# Schaltplan_V1_0.net
KiCad netlist of a schematic drawn in EAGLE
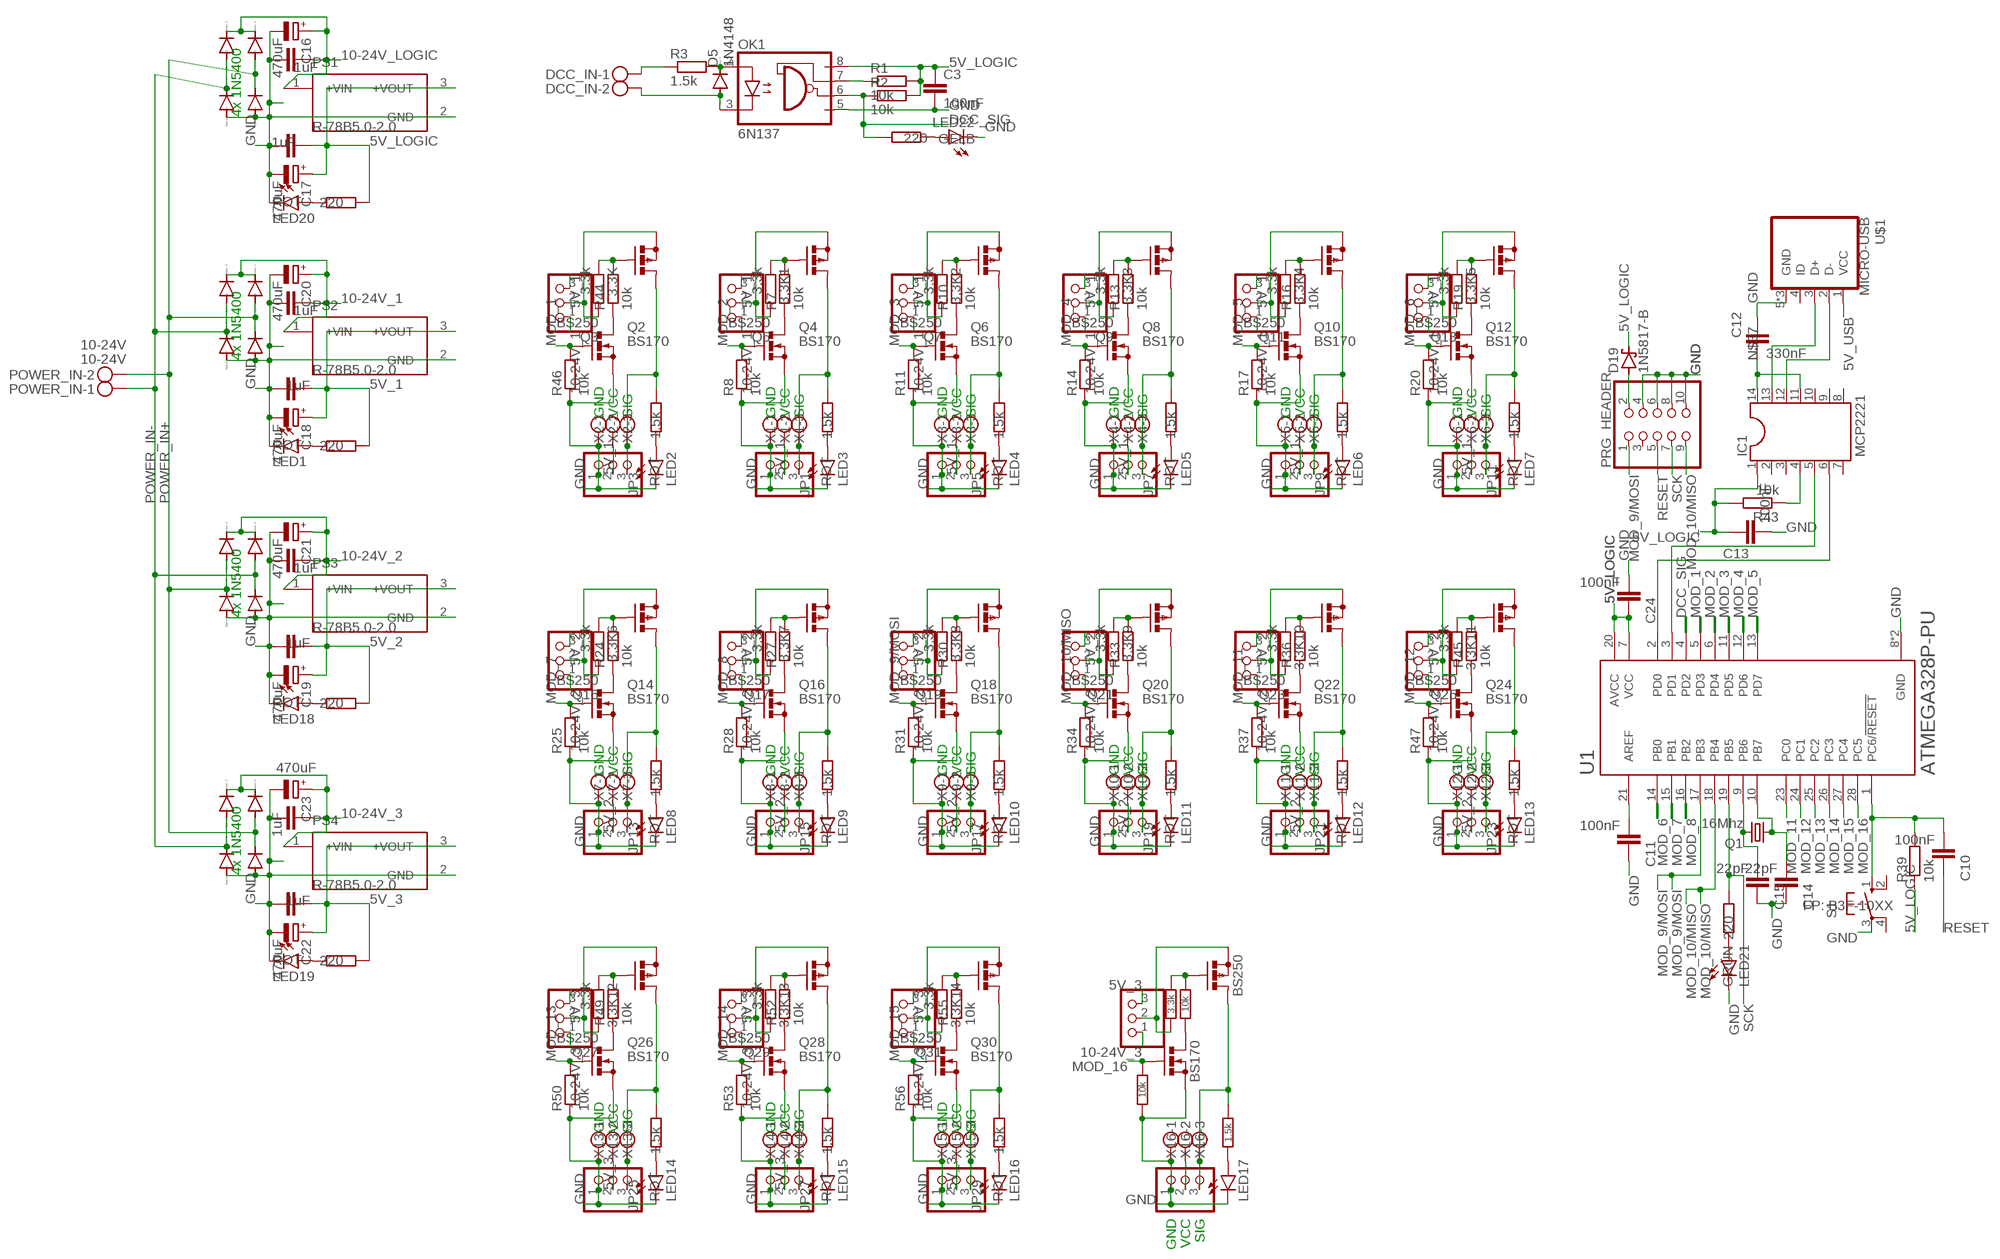
[diagram p0: schematic, sheet 1]

(export (version "E")
  (design (tool "Eeschema 10.0.6"))
  (components
    (comp (ref "3,3K")
      (value "3.3k")
      (footprint "eagle-import:0207_7")
      (libsource (lib "eagle-import") (part "R-EU_0207/7"))
    )
    (comp (ref "3,3K1")
      (value "3.3k")
      (footprint "eagle-import:0207_7")
      (libsource (lib "eagle-import") (part "R-EU_0207/7"))
    )
    (comp (ref "3,3K2")
      (value "3.3k")
      (footprint "eagle-import:0207_7")
      (libsource (lib "eagle-import") (part "R-EU_0207/7"))
    )
    (comp (ref "3,3K3")
      (value "3.3k")
      (footprint "eagle-import:0207_7")
      (libsource (lib "eagle-import") (part "R-EU_0207/7"))
    )
    (comp (ref "3,3K4")
      (value "3.3k")
      (footprint "eagle-import:0207_7")
      (libsource (lib "eagle-import") (part "R-EU_0207/7"))
    )
    (comp (ref "3,3K5")
      (value "3.3k")
      (footprint "eagle-import:0207_7")
      (libsource (lib "eagle-import") (part "R-EU_0207/7"))
    )
    (comp (ref "3,3K6")
      (value "3.3k")
      (footprint "eagle-import:0207_7")
      (libsource (lib "eagle-import") (part "R-EU_0207/7"))
    )
    (comp (ref "3,3K7")
      (value "3.3k")
      (footprint "eagle-import:0207_7")
      (libsource (lib "eagle-import") (part "R-EU_0207/7"))
    )
    (comp (ref "3,3K8")
      (value "3.3k")
      (footprint "eagle-import:0207_7")
      (libsource (lib "eagle-import") (part "R-EU_0207/7"))
    )
    (comp (ref "3,3K9")
      (value "3.3k")
      (footprint "eagle-import:0207_7")
      (libsource (lib "eagle-import") (part "R-EU_0207/7"))
    )
    (comp (ref "3,3K10")
      (value "3.3k")
      (footprint "eagle-import:0207_7")
      (libsource (lib "eagle-import") (part "R-EU_0207/7"))
    )
    (comp (ref "3,3K11")
      (value "3.3k")
      (footprint "eagle-import:0207_7")
      (libsource (lib "eagle-import") (part "R-EU_0207/7"))
    )
    (comp (ref "3,3K12")
      (value "3.3k")
      (footprint "eagle-import:0207_7")
      (libsource (lib "eagle-import") (part "R-EU_0207/7"))
    )
    (comp (ref "3,3K13")
      (value "3.3k")
      (footprint "eagle-import:0207_7")
      (libsource (lib "eagle-import") (part "R-EU_0207/7"))
    )
    (comp (ref "3,3K14")
      (value "3.3k")
      (footprint "eagle-import:0207_7")
      (libsource (lib "eagle-import") (part "R-EU_0207/7"))
    )
    (comp (ref "3,3K15")
      (value "3.3k")
      (footprint "eagle-import:0207_7")
      (libsource (lib "eagle-import") (part "R-EU_0207/7"))
    )
    (comp (ref "C1")
      (value "1uF")
      (footprint "eagle-import:C050-025X075")
      (libsource (lib "eagle-import") (part "C-EU050-025X075"))
    )
    (comp (ref "C2")
      (value "1uF")
      (footprint "eagle-import:C050-025X075")
      (libsource (lib "eagle-import") (part "C-EU050-025X075"))
    )
    (comp (ref "C3")
      (value "100nF")
      (footprint "eagle-import:C025-025X050")
      (libsource (lib "eagle-import") (part "C-EU025-025X050"))
    )
    (comp (ref "C4")
      (value "1uF")
      (footprint "eagle-import:C050-025X075")
      (libsource (lib "eagle-import") (part "C-EU050-025X075"))
    )
    (comp (ref "C5")
      (value "1uF")
      (footprint "eagle-import:C050-025X075")
      (libsource (lib "eagle-import") (part "C-EU050-025X075"))
    )
    (comp (ref "C6")
      (value "1uF")
      (footprint "eagle-import:C050-025X075")
      (libsource (lib "eagle-import") (part "C-EU050-025X075"))
    )
    (comp (ref "C7")
      (value "1uF")
      (footprint "eagle-import:C050-025X075")
      (libsource (lib "eagle-import") (part "C-EU050-025X075"))
    )
    (comp (ref "C8")
      (value "1uF")
      (footprint "eagle-import:C050-025X075")
      (libsource (lib "eagle-import") (part "C-EU050-025X075"))
    )
    (comp (ref "C9")
      (value "1uF")
      (footprint "eagle-import:C050-025X075")
      (libsource (lib "eagle-import") (part "C-EU050-025X075"))
    )
    (comp (ref "C10")
      (value "100nF")
      (footprint "eagle-import:C025-025X050")
      (libsource (lib "eagle-import") (part "C-EU025-025X050"))
    )
    (comp (ref "C11")
      (value "100nF")
      (footprint "eagle-import:C025-025X050")
      (libsource (lib "eagle-import") (part "C-EU025-025X050"))
    )
    (comp (ref "C12")
      (value "330nF")
      (footprint "eagle-import:C025-025X050")
      (libsource (lib "eagle-import") (part "C-EU025-025X050"))
    )
    (comp (ref "C13")
      (value "100nF")
      (footprint "eagle-import:C025-025X050")
      (libsource (lib "eagle-import") (part "C-EU025-025X050"))
    )
    (comp (ref "C14")
      (value "22pF")
      (footprint "eagle-import:C025-030X050")
      (libsource (lib "eagle-import") (part "C-EU025-030X050"))
    )
    (comp (ref "C15")
      (value "22pF")
      (footprint "eagle-import:C025-030X050")
      (libsource (lib "eagle-import") (part "C-EU025-030X050"))
    )
    (comp (ref "C16")
      (value "470uF")
      (footprint "eagle-import:E5-10,5")
      (libsource (lib "eagle-import") (part "CPOL-EUE5-10.5"))
    )
    (comp (ref "C17")
      (value "470uF")
      (footprint "eagle-import:E5-10,5")
      (libsource (lib "eagle-import") (part "CPOL-EUE5-10.5"))
    )
    (comp (ref "C18")
      (value "470uF")
      (footprint "eagle-import:E5-10,5")
      (libsource (lib "eagle-import") (part "CPOL-EUE5-10.5"))
    )
    (comp (ref "C19")
      (value "470uF")
      (footprint "eagle-import:E5-10,5")
      (libsource (lib "eagle-import") (part "CPOL-EUE5-10.5"))
    )
    (comp (ref "C20")
      (value "470uF")
      (footprint "eagle-import:E5-10,5")
      (libsource (lib "eagle-import") (part "CPOL-EUE5-10.5"))
    )
    (comp (ref "C21")
      (value "470uF")
      (footprint "eagle-import:E5-10,5")
      (libsource (lib "eagle-import") (part "CPOL-EUE5-10.5"))
    )
    (comp (ref "C22")
      (value "470uF")
      (footprint "eagle-import:E5-10,5")
      (libsource (lib "eagle-import") (part "CPOL-EUE5-10.5"))
    )
    (comp (ref "C23")
      (value "470uF")
      (footprint "eagle-import:E5-10,5")
      (libsource (lib "eagle-import") (part "CPOL-EUE5-10.5"))
    )
    (comp (ref "C24")
      (value "100nF")
      (footprint "eagle-import:C025-025X050")
      (libsource (lib "eagle-import") (part "C-EU025-025X050"))
    )
    (comp (ref "D1")
      (value "1N5400")
      (footprint "eagle-import:DO201-15")
      (libsource (lib "eagle-import") (part "1N5400"))
    )
    (comp (ref "D2")
      (value "1N5400")
      (footprint "eagle-import:DO201-15")
      (libsource (lib "eagle-import") (part "1N5400"))
    )
    (comp (ref "D3")
      (value "1N5400")
      (footprint "eagle-import:DO201-15")
      (libsource (lib "eagle-import") (part "1N5400"))
    )
    (comp (ref "D4")
      (value "1N5400")
      (footprint "eagle-import:DO201-15")
      (libsource (lib "eagle-import") (part "1N5400"))
    )
    (comp (ref "D5")
      (value "1N4148")
      (footprint "eagle-import:DO35-7")
      (libsource (lib "eagle-import") (part "1N4148DO35-7"))
    )
    (comp (ref "D6")
      (value "1N5400")
      (footprint "eagle-import:DO201-15")
      (libsource (lib "eagle-import") (part "1N5400"))
    )
    (comp (ref "D7")
      (value "1N5400")
      (footprint "eagle-import:DO201-15")
      (libsource (lib "eagle-import") (part "1N5400"))
    )
    (comp (ref "D8")
      (value "1N5400")
      (footprint "eagle-import:DO201-15")
      (libsource (lib "eagle-import") (part "1N5400"))
    )
    (comp (ref "D9")
      (value "1N5400")
      (footprint "eagle-import:DO201-15")
      (libsource (lib "eagle-import") (part "1N5400"))
    )
    (comp (ref "D10")
      (value "1N5400")
      (footprint "eagle-import:DO201-15")
      (libsource (lib "eagle-import") (part "1N5400"))
    )
    (comp (ref "D11")
      (value "1N5400")
      (footprint "eagle-import:DO201-15")
      (libsource (lib "eagle-import") (part "1N5400"))
    )
    (comp (ref "D12")
      (value "1N5400")
      (footprint "eagle-import:DO201-15")
      (libsource (lib "eagle-import") (part "1N5400"))
    )
    (comp (ref "D13")
      (value "1N5400")
      (footprint "eagle-import:DO201-15")
      (libsource (lib "eagle-import") (part "1N5400"))
    )
    (comp (ref "D14")
      (value "1N5400")
      (footprint "eagle-import:DO201-15")
      (libsource (lib "eagle-import") (part "1N5400"))
    )
    (comp (ref "D15")
      (value "1N5400")
      (footprint "eagle-import:DO201-15")
      (libsource (lib "eagle-import") (part "1N5400"))
    )
    (comp (ref "D16")
      (value "1N5400")
      (footprint "eagle-import:DO201-15")
      (libsource (lib "eagle-import") (part "1N5400"))
    )
    (comp (ref "D17")
      (value "1N5400")
      (footprint "eagle-import:DO201-15")
      (libsource (lib "eagle-import") (part "1N5400"))
    )
    (comp (ref "D19")
      (value "1N5817-B")
      (footprint "eagle-import:DO41-7.6")
      (libsource (lib "eagle-import") (part "1N5817-B"))
    )
    (comp (ref "DCC_IN")
      (value "MKDSN1,5/2-5,08")
      (footprint "eagle-import:MKDSN1,5_2-5,08")
      (libsource (lib "eagle-import") (part "MKDSN1,5/2-5,08"))
    )
    (comp (ref "IC1")
      (value "MCP2221")
      (footprint "eagle-import:DIL14")
      (libsource (lib "eagle-import") (part "DIL14"))
    )
    (comp (ref "JP1")
      (value "PINHD-1X3")
      (footprint "eagle-import:1X03")
      (libsource (lib "eagle-import") (part "PINHD-1X3"))
    )
    (comp (ref "JP2")
      (value "PINHD-1X3")
      (footprint "eagle-import:1X03")
      (libsource (lib "eagle-import") (part "PINHD-1X3"))
    )
    (comp (ref "JP3")
      (value "PINHD-1X3")
      (footprint "eagle-import:1X03")
      (libsource (lib "eagle-import") (part "PINHD-1X3"))
    )
    (comp (ref "JP4")
      (value "PINHD-1X3")
      (footprint "eagle-import:1X03")
      (libsource (lib "eagle-import") (part "PINHD-1X3"))
    )
    (comp (ref "JP5")
      (value "PINHD-1X3")
      (footprint "eagle-import:1X03")
      (libsource (lib "eagle-import") (part "PINHD-1X3"))
    )
    (comp (ref "JP6")
      (value "PINHD-1X3")
      (footprint "eagle-import:1X03")
      (libsource (lib "eagle-import") (part "PINHD-1X3"))
    )
    (comp (ref "JP7")
      (value "PINHD-1X3")
      (footprint "eagle-import:1X03")
      (libsource (lib "eagle-import") (part "PINHD-1X3"))
    )
    (comp (ref "JP8")
      (value "PINHD-1X3")
      (footprint "eagle-import:1X03")
      (libsource (lib "eagle-import") (part "PINHD-1X3"))
    )
    (comp (ref "JP9")
      (value "PINHD-1X3")
      (footprint "eagle-import:1X03")
      (libsource (lib "eagle-import") (part "PINHD-1X3"))
    )
    (comp (ref "JP10")
      (value "PINHD-1X3")
      (footprint "eagle-import:1X03")
      (libsource (lib "eagle-import") (part "PINHD-1X3"))
    )
    (comp (ref "JP11")
      (value "PINHD-1X3")
      (footprint "eagle-import:1X03")
      (libsource (lib "eagle-import") (part "PINHD-1X3"))
    )
    (comp (ref "JP12")
      (value "PINHD-1X3")
      (footprint "eagle-import:1X03")
      (libsource (lib "eagle-import") (part "PINHD-1X3"))
    )
    (comp (ref "JP13")
      (value "PINHD-1X3")
      (footprint "eagle-import:1X03")
      (libsource (lib "eagle-import") (part "PINHD-1X3"))
    )
    (comp (ref "JP14")
      (value "PINHD-1X3")
      (footprint "eagle-import:1X03")
      (libsource (lib "eagle-import") (part "PINHD-1X3"))
    )
    (comp (ref "JP15")
      (value "PINHD-1X3")
      (footprint "eagle-import:1X03")
      (libsource (lib "eagle-import") (part "PINHD-1X3"))
    )
    (comp (ref "JP16")
      (value "PINHD-1X3")
      (footprint "eagle-import:1X03")
      (libsource (lib "eagle-import") (part "PINHD-1X3"))
    )
    (comp (ref "JP17")
      (value "PINHD-1X3")
      (footprint "eagle-import:1X03")
      (libsource (lib "eagle-import") (part "PINHD-1X3"))
    )
    (comp (ref "JP18")
      (value "PINHD-1X3")
      (footprint "eagle-import:1X03")
      (libsource (lib "eagle-import") (part "PINHD-1X3"))
    )
    (comp (ref "JP19")
      (value "PINHD-1X3")
      (footprint "eagle-import:1X03")
      (libsource (lib "eagle-import") (part "PINHD-1X3"))
    )
    (comp (ref "JP20")
      (value "PINHD-1X3")
      (footprint "eagle-import:1X03")
      (libsource (lib "eagle-import") (part "PINHD-1X3"))
    )
    (comp (ref "JP21")
      (value "PINHD-1X3")
      (footprint "eagle-import:1X03")
      (libsource (lib "eagle-import") (part "PINHD-1X3"))
    )
    (comp (ref "JP22")
      (value "PINHD-1X3")
      (footprint "eagle-import:1X03")
      (libsource (lib "eagle-import") (part "PINHD-1X3"))
    )
    (comp (ref "JP23")
      (value "PINHD-1X3")
      (footprint "eagle-import:1X03")
      (libsource (lib "eagle-import") (part "PINHD-1X3"))
    )
    (comp (ref "JP24")
      (value "PINHD-1X3")
      (footprint "eagle-import:1X03")
      (libsource (lib "eagle-import") (part "PINHD-1X3"))
    )
    (comp (ref "JP25")
      (value "PINHD-1X3")
      (footprint "eagle-import:1X03")
      (libsource (lib "eagle-import") (part "PINHD-1X3"))
    )
    (comp (ref "JP26")
      (value "PINHD-1X3")
      (footprint "eagle-import:1X03")
      (libsource (lib "eagle-import") (part "PINHD-1X3"))
    )
    (comp (ref "JP27")
      (value "PINHD-1X3")
      (footprint "eagle-import:1X03")
      (libsource (lib "eagle-import") (part "PINHD-1X3"))
    )
    (comp (ref "JP28")
      (value "PINHD-1X3")
      (footprint "eagle-import:1X03")
      (libsource (lib "eagle-import") (part "PINHD-1X3"))
    )
    (comp (ref "JP29")
      (value "PINHD-1X3")
      (footprint "eagle-import:1X03")
      (libsource (lib "eagle-import") (part "PINHD-1X3"))
    )
    (comp (ref "JP30")
      (value "PINHD-1X3")
      (footprint "eagle-import:1X03")
      (libsource (lib "eagle-import") (part "PINHD-1X3"))
    )
    (comp (ref "JP31")
      (value "PINHD-1X3")
      (footprint "eagle-import:1X03")
      (libsource (lib "eagle-import") (part "PINHD-1X3"))
    )
    (comp (ref "JP32")
      (value "PINHD-1X3")
      (footprint "eagle-import:1X03")
      (libsource (lib "eagle-import") (part "PINHD-1X3"))
    )
    (comp (ref "LED1")
      (value "ROT")
      (footprint "eagle-import:LED3MM")
      (libsource (lib "eagle-import") (part "LED3MM"))
    )
    (comp (ref "LED2")
      (value "ROT")
      (footprint "eagle-import:LED3MM")
      (libsource (lib "eagle-import") (part "LED3MM"))
    )
    (comp (ref "LED3")
      (value "ROT")
      (footprint "eagle-import:LED3MM")
      (libsource (lib "eagle-import") (part "LED3MM"))
    )
    (comp (ref "LED4")
      (value "ROT")
      (footprint "eagle-import:LED3MM")
      (libsource (lib "eagle-import") (part "LED3MM"))
    )
    (comp (ref "LED5")
      (value "ROT")
      (footprint "eagle-import:LED3MM")
      (libsource (lib "eagle-import") (part "LED3MM"))
    )
    (comp (ref "LED6")
      (value "ROT")
      (footprint "eagle-import:LED3MM")
      (libsource (lib "eagle-import") (part "LED3MM"))
    )
    (comp (ref "LED7")
      (value "ROT")
      (footprint "eagle-import:LED3MM")
      (libsource (lib "eagle-import") (part "LED3MM"))
    )
    (comp (ref "LED8")
      (value "ROT")
      (footprint "eagle-import:LED3MM")
      (libsource (lib "eagle-import") (part "LED3MM"))
    )
    (comp (ref "LED9")
      (value "ROT")
      (footprint "eagle-import:LED3MM")
      (libsource (lib "eagle-import") (part "LED3MM"))
    )
    (comp (ref "LED10")
      (value "ROT")
      (footprint "eagle-import:LED3MM")
      (libsource (lib "eagle-import") (part "LED3MM"))
    )
    (comp (ref "LED11")
      (value "ROT")
      (footprint "eagle-import:LED3MM")
      (libsource (lib "eagle-import") (part "LED3MM"))
    )
    (comp (ref "LED12")
      (value "ROT")
      (footprint "eagle-import:LED3MM")
      (libsource (lib "eagle-import") (part "LED3MM"))
    )
    (comp (ref "LED13")
      (value "ROT")
      (footprint "eagle-import:LED3MM")
      (libsource (lib "eagle-import") (part "LED3MM"))
    )
    (comp (ref "LED14")
      (value "ROT")
      (footprint "eagle-import:LED3MM")
      (libsource (lib "eagle-import") (part "LED3MM"))
    )
    (comp (ref "LED15")
      (value "ROT")
      (footprint "eagle-import:LED3MM")
      (libsource (lib "eagle-import") (part "LED3MM"))
    )
    (comp (ref "LED16")
      (value "ROT")
      (footprint "eagle-import:LED3MM")
      (libsource (lib "eagle-import") (part "LED3MM"))
    )
    (comp (ref "LED17")
      (value "ROT")
      (footprint "eagle-import:LED3MM")
      (libsource (lib "eagle-import") (part "LED3MM"))
    )
    (comp (ref "LED18")
      (value "ROT")
      (footprint "eagle-import:LED3MM")
      (libsource (lib "eagle-import") (part "LED3MM"))
    )
    (comp (ref "LED19")
      (value "ROT")
      (footprint "eagle-import:LED3MM")
      (libsource (lib "eagle-import") (part "LED3MM"))
    )
    (comp (ref "LED20")
      (value "ROT")
      (footprint "eagle-import:LED3MM")
      (libsource (lib "eagle-import") (part "LED3MM"))
    )
    (comp (ref "LED21")
      (value "GRÜN")
      (footprint "eagle-import:LED3MM")
      (libsource (lib "eagle-import") (part "LED3MM"))
    )
    (comp (ref "LED22")
      (value "GELB")
      (footprint "eagle-import:LED3MM")
      (libsource (lib "eagle-import") (part "LED3MM"))
    )
    (comp (ref "OK1")
      (value "6N137")
      (footprint "eagle-import:DIL08")
      (libsource (lib "eagle-import") (part "6N137"))
    )
    (comp (ref "POWER_IN")
      (value "10-24V")
      (footprint "eagle-import:MKDSN1,5_2-5,08")
      (libsource (lib "eagle-import") (part "MKDSN1,5/2-5,08"))
    )
    (comp (ref "PRG_HEADER")
      (value "PINHD-2X5")
      (footprint "eagle-import:2X05")
      (libsource (lib "eagle-import") (part "PINHD-2X5"))
    )
    (comp (ref "PS1")
      (value "R-78B5.0-2.0")
      (footprint "eagle-import:CONV_R-78B5.0-2.0")
      (fields (field (name "MF") "Recom Power"))
      (libsource (lib "eagle-import") (part "R-78B5.0-2.0"))
    )
    (comp (ref "PS2")
      (value "R-78B5.0-2.0")
      (footprint "eagle-import:CONV_R-78B5.0-2.0")
      (fields (field (name "MF") "Recom Power"))
      (libsource (lib "eagle-import") (part "R-78B5.0-2.0"))
    )
    (comp (ref "PS3")
      (value "R-78B5.0-2.0")
      (footprint "eagle-import:CONV_R-78B5.0-2.0")
      (fields (field (name "MF") "Recom Power"))
      (libsource (lib "eagle-import") (part "R-78B5.0-2.0"))
    )
    (comp (ref "PS4")
      (value "R-78B5.0-2.0")
      (footprint "eagle-import:CONV_R-78B5.0-2.0")
      (fields (field (name "MF") "Recom Power"))
      (libsource (lib "eagle-import") (part "R-78B5.0-2.0"))
    )
    (comp (ref "Q1")
      (value "16Mhz")
      (footprint "eagle-import:HC49U-V")
      (libsource (lib "eagle-import") (part "CRYSTALHC49U-V"))
    )
    (comp (ref "Q2")
      (value "BS170")
      (footprint "eagle-import:SOT54E")
      (libsource (lib "eagle-import") (part "BS170"))
    )
    (comp (ref "Q3")
      (value "BS250")
      (footprint "eagle-import:SOT54E")
      (libsource (lib "eagle-import") (part "BS250"))
    )
    (comp (ref "Q4")
      (value "BS170")
      (footprint "eagle-import:SOT54E")
      (libsource (lib "eagle-import") (part "BS170"))
    )
    (comp (ref "Q5")
      (value "BS250")
      (footprint "eagle-import:SOT54E")
      (libsource (lib "eagle-import") (part "BS250"))
    )
    (comp (ref "Q6")
      (value "BS170")
      (footprint "eagle-import:SOT54E")
      (libsource (lib "eagle-import") (part "BS170"))
    )
    (comp (ref "Q7")
      (value "BS250")
      (footprint "eagle-import:SOT54E")
      (libsource (lib "eagle-import") (part "BS250"))
    )
    (comp (ref "Q8")
      (value "BS170")
      (footprint "eagle-import:SOT54E")
      (libsource (lib "eagle-import") (part "BS170"))
    )
    (comp (ref "Q9")
      (value "BS250")
      (footprint "eagle-import:SOT54E")
      (libsource (lib "eagle-import") (part "BS250"))
    )
    (comp (ref "Q10")
      (value "BS170")
      (footprint "eagle-import:SOT54E")
      (libsource (lib "eagle-import") (part "BS170"))
    )
    (comp (ref "Q11")
      (value "BS250")
      (footprint "eagle-import:SOT54E")
      (libsource (lib "eagle-import") (part "BS250"))
    )
    (comp (ref "Q12")
      (value "BS170")
      (footprint "eagle-import:SOT54E")
      (libsource (lib "eagle-import") (part "BS170"))
    )
    (comp (ref "Q13")
      (value "BS250")
      (footprint "eagle-import:SOT54E")
      (libsource (lib "eagle-import") (part "BS250"))
    )
    (comp (ref "Q14")
      (value "BS170")
      (footprint "eagle-import:SOT54E")
      (libsource (lib "eagle-import") (part "BS170"))
    )
    (comp (ref "Q15")
      (value "BS250")
      (footprint "eagle-import:SOT54E")
      (libsource (lib "eagle-import") (part "BS250"))
    )
    (comp (ref "Q16")
      (value "BS170")
      (footprint "eagle-import:SOT54E")
      (libsource (lib "eagle-import") (part "BS170"))
    )
    (comp (ref "Q17")
      (value "BS250")
      (footprint "eagle-import:SOT54E")
      (libsource (lib "eagle-import") (part "BS250"))
    )
    (comp (ref "Q18")
      (value "BS170")
      (footprint "eagle-import:SOT54E")
      (libsource (lib "eagle-import") (part "BS170"))
    )
    (comp (ref "Q19")
      (value "BS250")
      (footprint "eagle-import:SOT54E")
      (libsource (lib "eagle-import") (part "BS250"))
    )
    (comp (ref "Q20")
      (value "BS170")
      (footprint "eagle-import:SOT54E")
      (libsource (lib "eagle-import") (part "BS170"))
    )
    (comp (ref "Q21")
      (value "BS250")
      (footprint "eagle-import:SOT54E")
      (libsource (lib "eagle-import") (part "BS250"))
    )
    (comp (ref "Q22")
      (value "BS170")
      (footprint "eagle-import:SOT54E")
      (libsource (lib "eagle-import") (part "BS170"))
    )
    (comp (ref "Q23")
      (value "BS250")
      (footprint "eagle-import:SOT54E")
      (libsource (lib "eagle-import") (part "BS250"))
    )
    (comp (ref "Q24")
      (value "BS170")
      (footprint "eagle-import:SOT54E")
      (libsource (lib "eagle-import") (part "BS170"))
    )
    (comp (ref "Q25")
      (value "BS250")
      (footprint "eagle-import:SOT54E")
      (libsource (lib "eagle-import") (part "BS250"))
    )
    (comp (ref "Q26")
      (value "BS170")
      (footprint "eagle-import:SOT54E")
      (libsource (lib "eagle-import") (part "BS170"))
    )
    (comp (ref "Q27")
      (value "BS250")
      (footprint "eagle-import:SOT54E")
      (libsource (lib "eagle-import") (part "BS250"))
    )
    (comp (ref "Q28")
      (value "BS170")
      (footprint "eagle-import:SOT54E")
      (libsource (lib "eagle-import") (part "BS170"))
    )
    (comp (ref "Q29")
      (value "BS250")
      (footprint "eagle-import:SOT54E")
      (libsource (lib "eagle-import") (part "BS250"))
    )
    (comp (ref "Q30")
      (value "BS170")
      (footprint "eagle-import:SOT54E")
      (libsource (lib "eagle-import") (part "BS170"))
    )
    (comp (ref "Q31")
      (value "BS250")
      (footprint "eagle-import:SOT54E")
      (libsource (lib "eagle-import") (part "BS250"))
    )
    (comp (ref "Q32")
      (value "BS170")
      (footprint "eagle-import:SOT54E")
      (libsource (lib "eagle-import") (part "BS170"))
    )
    (comp (ref "Q33")
      (value "BS250")
      (footprint "eagle-import:SOT54E")
      (libsource (lib "eagle-import") (part "BS250"))
    )
    (comp (ref "R1")
      (value "10k")
      (footprint "eagle-import:0207_7")
      (libsource (lib "eagle-import") (part "R-EU_0207/7"))
    )
    (comp (ref "R2")
      (value "10k")
      (footprint "eagle-import:0207_7")
      (libsource (lib "eagle-import") (part "R-EU_0207/7"))
    )
    (comp (ref "R3")
      (value "1.5k")
      (footprint "eagle-import:0207_7")
      (libsource (lib "eagle-import") (part "R-EU_0207/7"))
    )
    (comp (ref "R4")
      (value "220")
      (footprint "eagle-import:0207_7")
      (libsource (lib "eagle-import") (part "R-EU_0207/7"))
    )
    (comp (ref "R5")
      (value "1.5k")
      (footprint "eagle-import:0207_7")
      (libsource (lib "eagle-import") (part "R-EU_0207/7"))
    )
    (comp (ref "R6")
      (value "1.5k")
      (footprint "eagle-import:0207_7")
      (libsource (lib "eagle-import") (part "R-EU_0207/7"))
    )
    (comp (ref "R7")
      (value "10k")
      (footprint "eagle-import:0207_7")
      (libsource (lib "eagle-import") (part "R-EU_0207/7"))
    )
    (comp (ref "R8")
      (value "10k")
      (footprint "eagle-import:0207_7")
      (libsource (lib "eagle-import") (part "R-EU_0207/7"))
    )
    (comp (ref "R9")
      (value "1.5k")
      (footprint "eagle-import:0207_7")
      (libsource (lib "eagle-import") (part "R-EU_0207/7"))
    )
    (comp (ref "R10")
      (value "10k")
      (footprint "eagle-import:0207_7")
      (libsource (lib "eagle-import") (part "R-EU_0207/7"))
    )
    (comp (ref "R11")
      (value "10k")
      (footprint "eagle-import:0207_7")
      (libsource (lib "eagle-import") (part "R-EU_0207/7"))
    )
    (comp (ref "R12")
      (value "1.5k")
      (footprint "eagle-import:0207_7")
      (libsource (lib "eagle-import") (part "R-EU_0207/7"))
    )
    (comp (ref "R13")
      (value "10k")
      (footprint "eagle-import:0207_7")
      (libsource (lib "eagle-import") (part "R-EU_0207/7"))
    )
    (comp (ref "R14")
      (value "10k")
      (footprint "eagle-import:0207_7")
      (libsource (lib "eagle-import") (part "R-EU_0207/7"))
    )
    (comp (ref "R15")
      (value "1.5k")
      (footprint "eagle-import:0207_7")
      (libsource (lib "eagle-import") (part "R-EU_0207/7"))
    )
    (comp (ref "R16")
      (value "10k")
      (footprint "eagle-import:0207_7")
      (libsource (lib "eagle-import") (part "R-EU_0207/7"))
    )
    (comp (ref "R17")
      (value "10k")
      (footprint "eagle-import:0207_7")
      (libsource (lib "eagle-import") (part "R-EU_0207/7"))
    )
    (comp (ref "R18")
      (value "1.5k")
      (footprint "eagle-import:0207_7")
      (libsource (lib "eagle-import") (part "R-EU_0207/7"))
    )
    (comp (ref "R19")
      (value "10k")
      (footprint "eagle-import:0207_7")
      (libsource (lib "eagle-import") (part "R-EU_0207/7"))
    )
    (comp (ref "R20")
      (value "10k")
      (footprint "eagle-import:0207_7")
      (libsource (lib "eagle-import") (part "R-EU_0207/7"))
    )
    (comp (ref "R21")
      (value "220")
      (footprint "eagle-import:0207_7")
      (libsource (lib "eagle-import") (part "R-EU_0207/7"))
    )
    (comp (ref "R22")
      (value "220")
      (footprint "eagle-import:0207_7")
      (libsource (lib "eagle-import") (part "R-EU_0207/7"))
    )
    (comp (ref "R23")
      (value "1.5k")
      (footprint "eagle-import:0207_7")
      (libsource (lib "eagle-import") (part "R-EU_0207/7"))
    )
    (comp (ref "R24")
      (value "10k")
      (footprint "eagle-import:0207_7")
      (libsource (lib "eagle-import") (part "R-EU_0207/7"))
    )
    (comp (ref "R25")
      (value "10k")
      (footprint "eagle-import:0207_7")
      (libsource (lib "eagle-import") (part "R-EU_0207/7"))
    )
    (comp (ref "R26")
      (value "1.5k")
      (footprint "eagle-import:0207_7")
      (libsource (lib "eagle-import") (part "R-EU_0207/7"))
    )
    (comp (ref "R27")
      (value "10k")
      (footprint "eagle-import:0207_7")
      (libsource (lib "eagle-import") (part "R-EU_0207/7"))
    )
    (comp (ref "R28")
      (value "10k")
      (footprint "eagle-import:0207_7")
      (libsource (lib "eagle-import") (part "R-EU_0207/7"))
    )
    (comp (ref "R29")
      (value "1.5k")
      (footprint "eagle-import:0207_7")
      (libsource (lib "eagle-import") (part "R-EU_0207/7"))
    )
    (comp (ref "R30")
      (value "10k")
      (footprint "eagle-import:0207_7")
      (libsource (lib "eagle-import") (part "R-EU_0207/7"))
    )
    (comp (ref "R31")
      (value "10k")
      (footprint "eagle-import:0207_7")
      (libsource (lib "eagle-import") (part "R-EU_0207/7"))
    )
    (comp (ref "R32")
      (value "1.5k")
      (footprint "eagle-import:0207_7")
      (libsource (lib "eagle-import") (part "R-EU_0207/7"))
    )
    (comp (ref "R33")
      (value "10k")
      (footprint "eagle-import:0207_7")
      (libsource (lib "eagle-import") (part "R-EU_0207/7"))
    )
    (comp (ref "R34")
      (value "10k")
      (footprint "eagle-import:0207_7")
      (libsource (lib "eagle-import") (part "R-EU_0207/7"))
    )
    (comp (ref "R35")
      (value "1.5k")
      (footprint "eagle-import:0207_7")
      (libsource (lib "eagle-import") (part "R-EU_0207/7"))
    )
    (comp (ref "R36")
      (value "10k")
      (footprint "eagle-import:0207_7")
      (libsource (lib "eagle-import") (part "R-EU_0207/7"))
    )
    (comp (ref "R37")
      (value "10k")
      (footprint "eagle-import:0207_7")
      (libsource (lib "eagle-import") (part "R-EU_0207/7"))
    )
    (comp (ref "R38")
      (value "1.5k")
      (footprint "eagle-import:0207_7")
      (libsource (lib "eagle-import") (part "R-EU_0207/7"))
    )
    (comp (ref "R39")
      (value "10k")
      (footprint "eagle-import:0207_7")
      (libsource (lib "eagle-import") (part "R-EU_0207/7"))
    )
    (comp (ref "R40")
      (value "220")
      (footprint "eagle-import:0207_7")
      (libsource (lib "eagle-import") (part "R-EU_0207/7"))
    )
    (comp (ref "R41")
      (value "220")
      (footprint "eagle-import:0207_7")
      (libsource (lib "eagle-import") (part "R-EU_0207/7"))
    )
    (comp (ref "R42")
      (value "220")
      (footprint "eagle-import:0207_7")
      (libsource (lib "eagle-import") (part "R-EU_0207/7"))
    )
    (comp (ref "R43")
      (value "10k")
      (footprint "eagle-import:0207_7")
      (libsource (lib "eagle-import") (part "R-EU_0207/7"))
    )
    (comp (ref "R44")
      (value "10k")
      (footprint "eagle-import:0207_7")
      (libsource (lib "eagle-import") (part "R-EU_0207/7"))
    )
    (comp (ref "R45")
      (value "10k")
      (footprint "eagle-import:0207_7")
      (libsource (lib "eagle-import") (part "R-EU_0207/7"))
    )
    (comp (ref "R46")
      (value "10k")
      (footprint "eagle-import:0207_7")
      (libsource (lib "eagle-import") (part "R-EU_0207/7"))
    )
    (comp (ref "R47")
      (value "10k")
      (footprint "eagle-import:0207_7")
      (libsource (lib "eagle-import") (part "R-EU_0207/7"))
    )
    (comp (ref "R48")
      (value "1.5k")
      (footprint "eagle-import:0207_7")
      (libsource (lib "eagle-import") (part "R-EU_0207/7"))
    )
    (comp (ref "R49")
      (value "10k")
      (footprint "eagle-import:0207_7")
      (libsource (lib "eagle-import") (part "R-EU_0207/7"))
    )
    (comp (ref "R50")
      (value "10k")
      (footprint "eagle-import:0207_7")
      (libsource (lib "eagle-import") (part "R-EU_0207/7"))
    )
    (comp (ref "R51")
      (value "1.5k")
      (footprint "eagle-import:0207_7")
      (libsource (lib "eagle-import") (part "R-EU_0207/7"))
    )
    (comp (ref "R52")
      (value "10k")
      (footprint "eagle-import:0207_7")
      (libsource (lib "eagle-import") (part "R-EU_0207/7"))
    )
    (comp (ref "R53")
      (value "10k")
      (footprint "eagle-import:0207_7")
      (libsource (lib "eagle-import") (part "R-EU_0207/7"))
    )
    (comp (ref "R54")
      (value "1.5k")
      (footprint "eagle-import:0207_7")
      (libsource (lib "eagle-import") (part "R-EU_0207/7"))
    )
    (comp (ref "R55")
      (value "10k")
      (footprint "eagle-import:0207_7")
      (libsource (lib "eagle-import") (part "R-EU_0207/7"))
    )
    (comp (ref "R56")
      (value "10k")
      (footprint "eagle-import:0207_7")
      (libsource (lib "eagle-import") (part "R-EU_0207/7"))
    )
    (comp (ref "R57")
      (value "1.5k")
      (footprint "eagle-import:0207_7")
      (libsource (lib "eagle-import") (part "R-EU_0207/7"))
    )
    (comp (ref "R58")
      (value "10k")
      (footprint "eagle-import:0207_7")
      (libsource (lib "eagle-import") (part "R-EU_0207/7"))
    )
    (comp (ref "R59")
      (value "10k")
      (footprint "eagle-import:0207_7")
      (libsource (lib "eagle-import") (part "R-EU_0207/7"))
    )
    (comp (ref "S1")
      (value "FP: B3F-10XX")
      (footprint "eagle-import:B3F-10XX")
      (fields (field (name "MPN") "B3F-1000"))
      (libsource (lib "eagle-import") (part "10-XX"))
    )
    (comp (ref "U$1")
      (value "MICRO-USB")
      (footprint "eagle-import:MICRO-USB")
      (libsource (lib "eagle-import") (part "MICRO-USB"))
    )
    (comp (ref "U1")
      (value "ATMEGA328P-PU")
      (footprint "eagle-import:DIP794W46P254L2967H457Q28B")
      (fields (field (name "MF") "Microchip"))
      (libsource (lib "eagle-import") (part "ATMEGA328P-PU"))
    )
    (comp (ref "X1")
      (value "MKDSN1,5/3-5,08")
      (footprint "eagle-import:MKDSN1,5_3-5,08")
      (libsource (lib "eagle-import") (part "MKDSN1,5/3-5,08"))
    )
    (comp (ref "X2")
      (value "MKDSN1,5/3-5,08")
      (footprint "eagle-import:MKDSN1,5_3-5,08")
      (libsource (lib "eagle-import") (part "MKDSN1,5/3-5,08"))
    )
    (comp (ref "X3")
      (value "MKDSN1,5/3-5,08")
      (footprint "eagle-import:MKDSN1,5_3-5,08")
      (libsource (lib "eagle-import") (part "MKDSN1,5/3-5,08"))
    )
    (comp (ref "X4")
      (value "MKDSN1,5/3-5,08")
      (footprint "eagle-import:MKDSN1,5_3-5,08")
      (libsource (lib "eagle-import") (part "MKDSN1,5/3-5,08"))
    )
    (comp (ref "X5")
      (value "MKDSN1,5/3-5,08")
      (footprint "eagle-import:MKDSN1,5_3-5,08")
      (libsource (lib "eagle-import") (part "MKDSN1,5/3-5,08"))
    )
    (comp (ref "X6")
      (value "MKDSN1,5/3-5,08")
      (footprint "eagle-import:MKDSN1,5_3-5,08")
      (libsource (lib "eagle-import") (part "MKDSN1,5/3-5,08"))
    )
    (comp (ref "X7")
      (value "MKDSN1,5/3-5,08")
      (footprint "eagle-import:MKDSN1,5_3-5,08")
      (libsource (lib "eagle-import") (part "MKDSN1,5/3-5,08"))
    )
    (comp (ref "X8")
      (value "MKDSN1,5/3-5,08")
      (footprint "eagle-import:MKDSN1,5_3-5,08")
      (libsource (lib "eagle-import") (part "MKDSN1,5/3-5,08"))
    )
    (comp (ref "X9")
      (value "MKDSN1,5/3-5,08")
      (footprint "eagle-import:MKDSN1,5_3-5,08")
      (libsource (lib "eagle-import") (part "MKDSN1,5/3-5,08"))
    )
    (comp (ref "X10")
      (value "MKDSN1,5/3-5,08")
      (footprint "eagle-import:MKDSN1,5_3-5,08")
      (libsource (lib "eagle-import") (part "MKDSN1,5/3-5,08"))
    )
    (comp (ref "X11")
      (value "MKDSN1,5/3-5,08")
      (footprint "eagle-import:MKDSN1,5_3-5,08")
      (libsource (lib "eagle-import") (part "MKDSN1,5/3-5,08"))
    )
    (comp (ref "X12")
      (value "MKDSN1,5/3-5,08")
      (footprint "eagle-import:MKDSN1,5_3-5,08")
      (libsource (lib "eagle-import") (part "MKDSN1,5/3-5,08"))
    )
    (comp (ref "X13")
      (value "MKDSN1,5/3-5,08")
      (footprint "eagle-import:MKDSN1,5_3-5,08")
      (libsource (lib "eagle-import") (part "MKDSN1,5/3-5,08"))
    )
    (comp (ref "X14")
      (value "MKDSN1,5/3-5,08")
      (footprint "eagle-import:MKDSN1,5_3-5,08")
      (libsource (lib "eagle-import") (part "MKDSN1,5/3-5,08"))
    )
    (comp (ref "X15")
      (value "MKDSN1,5/3-5,08")
      (footprint "eagle-import:MKDSN1,5_3-5,08")
      (libsource (lib "eagle-import") (part "MKDSN1,5/3-5,08"))
    )
    (comp (ref "X16")
      (value "MKDSN1,5/3-5,08")
      (footprint "eagle-import:MKDSN1,5_3-5,08")
      (libsource (lib "eagle-import") (part "MKDSN1,5/3-5,08"))
    )
  )
  (nets
    (net (code "1") (name "/5V_1") (class "Default")
      (node (ref "C1") (pin "2") (pinfunction "2_2") (pintype "passive"))
      (node (ref "C18") (pin "+") (pinfunction "+_+") (pintype "passive"))
      (node (ref "JP1") (pin "2") (pinfunction "2_2") (pintype "passive"))
      (node (ref "JP10") (pin "3") (pinfunction "3_3") (pintype "passive"))
      (node (ref "JP11") (pin "2") (pinfunction "2_2") (pintype "passive"))
      (node (ref "JP12") (pin "3") (pinfunction "3_3") (pintype "passive"))
      (node (ref "JP2") (pin "3") (pinfunction "3_3") (pintype "passive"))
      (node (ref "JP3") (pin "2") (pinfunction "2_2") (pintype "passive"))
      (node (ref "JP4") (pin "3") (pinfunction "3_3") (pintype "passive"))
      (node (ref "JP5") (pin "2") (pinfunction "2_2") (pintype "passive"))
      (node (ref "JP6") (pin "3") (pinfunction "3_3") (pintype "passive"))
      (node (ref "JP7") (pin "2") (pinfunction "2_2") (pintype "passive"))
      (node (ref "JP8") (pin "3") (pinfunction "3_3") (pintype "passive"))
      (node (ref "JP9") (pin "2") (pinfunction "2_2") (pintype "passive"))
      (node (ref "PS2") (pin "3") (pinfunction "+VOUT_3") (pintype "output"))
      (node (ref "R4") (pin "2") (pinfunction "2_2") (pintype "passive"))
      (node (ref "X1") (pin "2") (pinfunction "KL_2") (pintype "passive"))
      (node (ref "X2") (pin "2") (pinfunction "KL_2") (pintype "passive"))
      (node (ref "X3") (pin "2") (pinfunction "KL_2") (pintype "passive"))
      (node (ref "X4") (pin "2") (pinfunction "KL_2") (pintype "passive"))
      (node (ref "X5") (pin "2") (pinfunction "KL_2") (pintype "passive"))
      (node (ref "X6") (pin "2") (pinfunction "KL_2") (pintype "passive"))
    )
    (net (code "2") (name "/5V_2") (class "Default")
      (node (ref "C19") (pin "+") (pinfunction "+_+") (pintype "passive"))
      (node (ref "C4") (pin "2") (pinfunction "2_2") (pintype "passive"))
      (node (ref "JP13") (pin "2") (pinfunction "2_2") (pintype "passive"))
      (node (ref "JP14") (pin "3") (pinfunction "3_3") (pintype "passive"))
      (node (ref "JP15") (pin "2") (pinfunction "2_2") (pintype "passive"))
      (node (ref "JP16") (pin "3") (pinfunction "3_3") (pintype "passive"))
      (node (ref "JP17") (pin "2") (pinfunction "2_2") (pintype "passive"))
      (node (ref "JP18") (pin "3") (pinfunction "3_3") (pintype "passive"))
      (node (ref "JP19") (pin "2") (pinfunction "2_2") (pintype "passive"))
      (node (ref "JP20") (pin "3") (pinfunction "3_3") (pintype "passive"))
      (node (ref "JP21") (pin "2") (pinfunction "2_2") (pintype "passive"))
      (node (ref "JP22") (pin "3") (pinfunction "3_3") (pintype "passive"))
      (node (ref "JP23") (pin "2") (pinfunction "2_2") (pintype "passive"))
      (node (ref "JP24") (pin "3") (pinfunction "3_3") (pintype "passive"))
      (node (ref "PS3") (pin "3") (pinfunction "+VOUT_3") (pintype "output"))
      (node (ref "R21") (pin "2") (pinfunction "2_2") (pintype "passive"))
      (node (ref "X10") (pin "2") (pinfunction "KL_2") (pintype "passive"))
      (node (ref "X11") (pin "2") (pinfunction "KL_2") (pintype "passive"))
      (node (ref "X12") (pin "2") (pinfunction "KL_2") (pintype "passive"))
      (node (ref "X7") (pin "2") (pinfunction "KL_2") (pintype "passive"))
      (node (ref "X8") (pin "2") (pinfunction "KL_2") (pintype "passive"))
      (node (ref "X9") (pin "2") (pinfunction "KL_2") (pintype "passive"))
    )
    (net (code "3") (name "/5V_3") (class "Default")
      (node (ref "C22") (pin "+") (pinfunction "+_+") (pintype "passive"))
      (node (ref "C6") (pin "2") (pinfunction "2_2") (pintype "passive"))
      (node (ref "JP25") (pin "2") (pinfunction "2_2") (pintype "passive"))
      (node (ref "JP26") (pin "3") (pinfunction "3_3") (pintype "passive"))
      (node (ref "JP27") (pin "2") (pinfunction "2_2") (pintype "passive"))
      (node (ref "JP28") (pin "3") (pinfunction "3_3") (pintype "passive"))
      (node (ref "JP29") (pin "2") (pinfunction "2_2") (pintype "passive"))
      (node (ref "JP30") (pin "3") (pinfunction "3_3") (pintype "passive"))
      (node (ref "JP31") (pin "2") (pinfunction "2_2") (pintype "passive"))
      (node (ref "JP32") (pin "3") (pinfunction "3_3") (pintype "passive"))
      (node (ref "PS4") (pin "3") (pinfunction "+VOUT_3") (pintype "output"))
      (node (ref "R22") (pin "2") (pinfunction "2_2") (pintype "passive"))
      (node (ref "X13") (pin "2") (pinfunction "KL_2") (pintype "passive"))
      (node (ref "X14") (pin "2") (pinfunction "KL_2") (pintype "passive"))
      (node (ref "X15") (pin "2") (pinfunction "KL_2") (pintype "passive"))
      (node (ref "X16") (pin "2") (pinfunction "KL_2") (pintype "passive"))
    )
    (net (code "4") (name "/5V_LOGIC") (class "Default")
      (node (ref "C13") (pin "1") (pinfunction "1_1") (pintype "passive"))
      (node (ref "C17") (pin "+") (pinfunction "+_+") (pintype "passive"))
      (node (ref "C24") (pin "1") (pinfunction "1_1") (pintype "passive"))
      (node (ref "C3") (pin "1") (pinfunction "1_1") (pintype "passive"))
      (node (ref "C8") (pin "2") (pinfunction "2_2") (pintype "passive"))
      (node (ref "D19") (pin "C") (pinfunction "C_C") (pintype "passive"))
      (node (ref "IC1") (pin "1") (pinfunction "1_1") (pintype "passive"))
      (node (ref "OK1") (pin "8") (pinfunction "VCC_8") (pintype "passive"))
      (node (ref "PS1") (pin "3") (pinfunction "+VOUT_3") (pintype "output"))
      (node (ref "R1") (pin "2") (pinfunction "2_2") (pintype "passive"))
      (node (ref "R2") (pin "2") (pinfunction "2_2") (pintype "passive"))
      (node (ref "R39") (pin "1") (pinfunction "1_1") (pintype "passive"))
      (node (ref "R40") (pin "2") (pinfunction "2_2") (pintype "passive"))
      (node (ref "R43") (pin "2") (pinfunction "2_2") (pintype "passive"))
      (node (ref "U1") (pin "20") (pinfunction "AVCC_20") (pintype "power_in"))
      (node (ref "U1") (pin "7") (pinfunction "VCC_7") (pintype "power_in"))
    )
    (net (code "5") (name "/5V_USB") (class "Default")
      (node (ref "U$1") (pin "1") (pinfunction "VCC_1") (pintype "power_in"))
    )
    (net (code "6") (name "/10-24V_1") (class "Default")
      (node (ref "C2") (pin "2") (pinfunction "2_2") (pintype "passive"))
      (node (ref "C20") (pin "+") (pinfunction "+_+") (pintype "passive"))
      (node (ref "D1") (pin "C") (pinfunction "C_C") (pintype "passive"))
      (node (ref "D3") (pin "C") (pinfunction "C_C") (pintype "passive"))
      (node (ref "JP10") (pin "1") (pinfunction "1_1") (pintype "passive"))
      (node (ref "JP12") (pin "1") (pinfunction "1_1") (pintype "passive"))
      (node (ref "JP2") (pin "1") (pinfunction "1_1") (pintype "passive"))
      (node (ref "JP4") (pin "1") (pinfunction "1_1") (pintype "passive"))
      (node (ref "JP6") (pin "1") (pinfunction "1_1") (pintype "passive"))
      (node (ref "JP8") (pin "1") (pinfunction "1_1") (pintype "passive"))
      (node (ref "PS2") (pin "1") (pinfunction "+VIN_1") (pintype "input"))
    )
    (net (code "7") (name "/10-24V_2") (class "Default")
      (node (ref "C21") (pin "+") (pinfunction "+_+") (pintype "passive"))
      (node (ref "C5") (pin "2") (pinfunction "2_2") (pintype "passive"))
      (node (ref "D6") (pin "C") (pinfunction "C_C") (pintype "passive"))
      (node (ref "D8") (pin "C") (pinfunction "C_C") (pintype "passive"))
      (node (ref "JP14") (pin "1") (pinfunction "1_1") (pintype "passive"))
      (node (ref "JP16") (pin "1") (pinfunction "1_1") (pintype "passive"))
      (node (ref "JP18") (pin "1") (pinfunction "1_1") (pintype "passive"))
      (node (ref "JP20") (pin "1") (pinfunction "1_1") (pintype "passive"))
      (node (ref "JP22") (pin "1") (pinfunction "1_1") (pintype "passive"))
      (node (ref "JP24") (pin "1") (pinfunction "1_1") (pintype "passive"))
      (node (ref "PS3") (pin "1") (pinfunction "+VIN_1") (pintype "input"))
    )
    (net (code "8") (name "/10-24V_3") (class "Default")
      (node (ref "C23") (pin "+") (pinfunction "+_+") (pintype "passive"))
      (node (ref "C7") (pin "2") (pinfunction "2_2") (pintype "passive"))
      (node (ref "D10") (pin "C") (pinfunction "C_C") (pintype "passive"))
      (node (ref "D12") (pin "C") (pinfunction "C_C") (pintype "passive"))
      (node (ref "JP26") (pin "1") (pinfunction "1_1") (pintype "passive"))
      (node (ref "JP28") (pin "1") (pinfunction "1_1") (pintype "passive"))
      (node (ref "JP30") (pin "1") (pinfunction "1_1") (pintype "passive"))
      (node (ref "JP32") (pin "1") (pinfunction "1_1") (pintype "passive"))
      (node (ref "PS4") (pin "1") (pinfunction "+VIN_1") (pintype "input"))
    )
    (net (code "9") (name "/10-24V_LOGIC") (class "Default")
      (node (ref "C16") (pin "+") (pinfunction "+_+") (pintype "passive"))
      (node (ref "C9") (pin "2") (pinfunction "2_2") (pintype "passive"))
      (node (ref "D14") (pin "C") (pinfunction "C_C") (pintype "passive"))
      (node (ref "D16") (pin "C") (pinfunction "C_C") (pintype "passive"))
      (node (ref "PS1") (pin "1") (pinfunction "+VIN_1") (pintype "input"))
    )
    (net (code "10") (name "/DCC_SIG") (class "Default")
      (node (ref "OK1") (pin "6") (pinfunction "VO_6") (pintype "passive"))
      (node (ref "R2") (pin "1") (pinfunction "1_1") (pintype "passive"))
      (node (ref "R42") (pin "2") (pinfunction "2_2") (pintype "passive"))
      (node (ref "U1") (pin "4") (pinfunction "PD2_4") (pintype "bidirectional"))
    )
    (net (code "11") (name "/GND") (class "Default")
      (node (ref "C1") (pin "1") (pinfunction "1_1") (pintype "passive"))
      (node (ref "C11") (pin "1") (pinfunction "1_1") (pintype "passive"))
      (node (ref "C12") (pin "1") (pinfunction "1_1") (pintype "passive"))
      (node (ref "C13") (pin "2") (pinfunction "2_2") (pintype "passive"))
      (node (ref "C14") (pin "1") (pinfunction "1_1") (pintype "passive"))
      (node (ref "C15") (pin "1") (pinfunction "1_1") (pintype "passive"))
      (node (ref "C16") (pin "-") (pinfunction "-_-") (pintype "passive"))
      (node (ref "C17") (pin "-") (pinfunction "-_-") (pintype "passive"))
      (node (ref "C18") (pin "-") (pinfunction "-_-") (pintype "passive"))
      (node (ref "C19") (pin "-") (pinfunction "-_-") (pintype "passive"))
      (node (ref "C2") (pin "1") (pinfunction "1_1") (pintype "passive"))
      (node (ref "C20") (pin "-") (pinfunction "-_-") (pintype "passive"))
      (node (ref "C21") (pin "-") (pinfunction "-_-") (pintype "passive"))
      (node (ref "C22") (pin "-") (pinfunction "-_-") (pintype "passive"))
      (node (ref "C23") (pin "-") (pinfunction "-_-") (pintype "passive"))
      (node (ref "C24") (pin "2") (pinfunction "2_2") (pintype "passive"))
      (node (ref "C3") (pin "2") (pinfunction "2_2") (pintype "passive"))
      (node (ref "C4") (pin "1") (pinfunction "1_1") (pintype "passive"))
      (node (ref "C5") (pin "1") (pinfunction "1_1") (pintype "passive"))
      (node (ref "C6") (pin "1") (pinfunction "1_1") (pintype "passive"))
      (node (ref "C7") (pin "1") (pinfunction "1_1") (pintype "passive"))
      (node (ref "C8") (pin "1") (pinfunction "1_1") (pintype "passive"))
      (node (ref "C9") (pin "1") (pinfunction "1_1") (pintype "passive"))
      (node (ref "D11") (pin "A") (pinfunction "A_A") (pintype "passive"))
      (node (ref "D13") (pin "A") (pinfunction "A_A") (pintype "passive"))
      (node (ref "D15") (pin "A") (pinfunction "A_A") (pintype "passive"))
      (node (ref "D17") (pin "A") (pinfunction "A_A") (pintype "passive"))
      (node (ref "D2") (pin "A") (pinfunction "A_A") (pintype "passive"))
      (node (ref "D4") (pin "A") (pinfunction "A_A") (pintype "passive"))
      (node (ref "D7") (pin "A") (pinfunction "A_A") (pintype "passive"))
      (node (ref "D9") (pin "A") (pinfunction "A_A") (pintype "passive"))
      (node (ref "JP1") (pin "1") (pinfunction "1_1") (pintype "passive"))
      (node (ref "JP11") (pin "1") (pinfunction "1_1") (pintype "passive"))
      (node (ref "JP13") (pin "1") (pinfunction "1_1") (pintype "passive"))
      (node (ref "JP15") (pin "1") (pinfunction "1_1") (pintype "passive"))
      (node (ref "JP17") (pin "1") (pinfunction "1_1") (pintype "passive"))
      (node (ref "JP19") (pin "1") (pinfunction "1_1") (pintype "passive"))
      (node (ref "JP21") (pin "1") (pinfunction "1_1") (pintype "passive"))
      (node (ref "JP23") (pin "1") (pinfunction "1_1") (pintype "passive"))
      (node (ref "JP25") (pin "1") (pinfunction "1_1") (pintype "passive"))
      (node (ref "JP27") (pin "1") (pinfunction "1_1") (pintype "passive"))
      (node (ref "JP29") (pin "1") (pinfunction "1_1") (pintype "passive"))
      (node (ref "JP3") (pin "1") (pinfunction "1_1") (pintype "passive"))
      (node (ref "JP31") (pin "1") (pinfunction "1_1") (pintype "passive"))
      (node (ref "JP5") (pin "1") (pinfunction "1_1") (pintype "passive"))
      (node (ref "JP7") (pin "1") (pinfunction "1_1") (pintype "passive"))
      (node (ref "JP9") (pin "1") (pinfunction "1_1") (pintype "passive"))
      (node (ref "LED1") (pin "K") (pinfunction "C_K") (pintype "passive"))
      (node (ref "LED10") (pin "K") (pinfunction "C_K") (pintype "passive"))
      (node (ref "LED11") (pin "K") (pinfunction "C_K") (pintype "passive"))
      (node (ref "LED12") (pin "K") (pinfunction "C_K") (pintype "passive"))
      (node (ref "LED13") (pin "K") (pinfunction "C_K") (pintype "passive"))
      (node (ref "LED14") (pin "K") (pinfunction "C_K") (pintype "passive"))
      (node (ref "LED15") (pin "K") (pinfunction "C_K") (pintype "passive"))
      (node (ref "LED16") (pin "K") (pinfunction "C_K") (pintype "passive"))
      (node (ref "LED17") (pin "K") (pinfunction "C_K") (pintype "passive"))
      (node (ref "LED18") (pin "K") (pinfunction "C_K") (pintype "passive"))
      (node (ref "LED19") (pin "K") (pinfunction "C_K") (pintype "passive"))
      (node (ref "LED2") (pin "K") (pinfunction "C_K") (pintype "passive"))
      (node (ref "LED20") (pin "K") (pinfunction "C_K") (pintype "passive"))
      (node (ref "LED21") (pin "K") (pinfunction "C_K") (pintype "passive"))
      (node (ref "LED22") (pin "K") (pinfunction "C_K") (pintype "passive"))
      (node (ref "LED3") (pin "K") (pinfunction "C_K") (pintype "passive"))
      (node (ref "LED4") (pin "K") (pinfunction "C_K") (pintype "passive"))
      (node (ref "LED5") (pin "K") (pinfunction "C_K") (pintype "passive"))
      (node (ref "LED6") (pin "K") (pinfunction "C_K") (pintype "passive"))
      (node (ref "LED7") (pin "K") (pinfunction "C_K") (pintype "passive"))
      (node (ref "LED8") (pin "K") (pinfunction "C_K") (pintype "passive"))
      (node (ref "LED9") (pin "K") (pinfunction "C_K") (pintype "passive"))
      (node (ref "OK1") (pin "5") (pinfunction "GND_5") (pintype "passive"))
      (node (ref "PRG_HEADER") (pin "10") (pinfunction "10_10") (pintype "passive"))
      (node (ref "PRG_HEADER") (pin "4") (pinfunction "4_4") (pintype "passive"))
      (node (ref "PRG_HEADER") (pin "6") (pinfunction "6_6") (pintype "passive"))
      (node (ref "PRG_HEADER") (pin "8") (pinfunction "8_8") (pintype "passive"))
      (node (ref "PS1") (pin "2") (pinfunction "GND_2") (pintype "power_in"))
      (node (ref "PS2") (pin "2") (pinfunction "GND_2") (pintype "power_in"))
      (node (ref "PS3") (pin "2") (pinfunction "GND_2") (pintype "power_in"))
      (node (ref "PS4") (pin "2") (pinfunction "GND_2") (pintype "power_in"))
      (node (ref "Q10") (pin "S") (pinfunction "S_S") (pintype "passive"))
      (node (ref "Q12") (pin "S") (pinfunction "S_S") (pintype "passive"))
      (node (ref "Q14") (pin "S") (pinfunction "S_S") (pintype "passive"))
      (node (ref "Q16") (pin "S") (pinfunction "S_S") (pintype "passive"))
      (node (ref "Q18") (pin "S") (pinfunction "S_S") (pintype "passive"))
      (node (ref "Q2") (pin "S") (pinfunction "S_S") (pintype "passive"))
      (node (ref "Q20") (pin "S") (pinfunction "S_S") (pintype "passive"))
      (node (ref "Q22") (pin "S") (pinfunction "S_S") (pintype "passive"))
      (node (ref "Q24") (pin "S") (pinfunction "S_S") (pintype "passive"))
      (node (ref "Q26") (pin "S") (pinfunction "S_S") (pintype "passive"))
      (node (ref "Q28") (pin "S") (pinfunction "S_S") (pintype "passive"))
      (node (ref "Q30") (pin "S") (pinfunction "S_S") (pintype "passive"))
      (node (ref "Q32") (pin "S") (pinfunction "S_S") (pintype "passive"))
      (node (ref "Q4") (pin "S") (pinfunction "S_S") (pintype "passive"))
      (node (ref "Q6") (pin "S") (pinfunction "S_S") (pintype "passive"))
      (node (ref "Q8") (pin "S") (pinfunction "S_S") (pintype "passive"))
      (node (ref "R11") (pin "1") (pinfunction "1_1") (pintype "passive"))
      (node (ref "R14") (pin "1") (pinfunction "1_1") (pintype "passive"))
      (node (ref "R17") (pin "1") (pinfunction "1_1") (pintype "passive"))
      (node (ref "R20") (pin "1") (pinfunction "1_1") (pintype "passive"))
      (node (ref "R25") (pin "1") (pinfunction "1_1") (pintype "passive"))
      (node (ref "R28") (pin "1") (pinfunction "1_1") (pintype "passive"))
      (node (ref "R31") (pin "1") (pinfunction "1_1") (pintype "passive"))
      (node (ref "R34") (pin "1") (pinfunction "1_1") (pintype "passive"))
      (node (ref "R37") (pin "1") (pinfunction "1_1") (pintype "passive"))
      (node (ref "R46") (pin "1") (pinfunction "1_1") (pintype "passive"))
      (node (ref "R47") (pin "1") (pinfunction "1_1") (pintype "passive"))
      (node (ref "R50") (pin "1") (pinfunction "1_1") (pintype "passive"))
      (node (ref "R53") (pin "1") (pinfunction "1_1") (pintype "passive"))
      (node (ref "R56") (pin "1") (pinfunction "1_1") (pintype "passive"))
      (node (ref "R59") (pin "1") (pinfunction "1_1") (pintype "passive"))
      (node (ref "R8") (pin "1") (pinfunction "1_1") (pintype "passive"))
      (node (ref "S1") (pin "3") (pinfunction "P_3") (pintype "passive"))
      (node (ref "U$1") (pin "5") (pinfunction "GND_5") (pintype "power_in"))
      (node (ref "U$1") (pin "GND1") (pinfunction "GND_GND1") (pintype "power_in"))
      (node (ref "U$1") (pin "GND2") (pinfunction "GND_GND2") (pintype "power_in"))
      (node (ref "U1") (pin "22") (pinfunction "GND_22") (pintype "power_in"))
      (node (ref "U1") (pin "8") (pinfunction "GND_8") (pintype "power_in"))
      (node (ref "X1") (pin "1") (pinfunction "KL_1") (pintype "passive"))
      (node (ref "X10") (pin "1") (pinfunction "KL_1") (pintype "passive"))
      (node (ref "X11") (pin "1") (pinfunction "KL_1") (pintype "passive"))
      (node (ref "X12") (pin "1") (pinfunction "KL_1") (pintype "passive"))
      (node (ref "X13") (pin "1") (pinfunction "KL_1") (pintype "passive"))
      (node (ref "X14") (pin "1") (pinfunction "KL_1") (pintype "passive"))
      (node (ref "X15") (pin "1") (pinfunction "KL_1") (pintype "passive"))
      (node (ref "X16") (pin "1") (pinfunction "KL_1") (pintype "passive"))
      (node (ref "X2") (pin "1") (pinfunction "KL_1") (pintype "passive"))
      (node (ref "X3") (pin "1") (pinfunction "KL_1") (pintype "passive"))
      (node (ref "X4") (pin "1") (pinfunction "KL_1") (pintype "passive"))
      (node (ref "X5") (pin "1") (pinfunction "KL_1") (pintype "passive"))
      (node (ref "X6") (pin "1") (pinfunction "KL_1") (pintype "passive"))
      (node (ref "X7") (pin "1") (pinfunction "KL_1") (pintype "passive"))
      (node (ref "X8") (pin "1") (pinfunction "KL_1") (pintype "passive"))
      (node (ref "X9") (pin "1") (pinfunction "KL_1") (pintype "passive"))
    )
    (net (code "12") (name "/MOD_1") (class "Default")
      (node (ref "Q2") (pin "G") (pinfunction "G_G") (pintype "passive"))
      (node (ref "R46") (pin "2") (pinfunction "2_2") (pintype "passive"))
      (node (ref "U1") (pin "5") (pinfunction "PD3_5") (pintype "bidirectional"))
    )
    (net (code "13") (name "/MOD_2") (class "Default")
      (node (ref "Q4") (pin "G") (pinfunction "G_G") (pintype "passive"))
      (node (ref "R8") (pin "2") (pinfunction "2_2") (pintype "passive"))
      (node (ref "U1") (pin "6") (pinfunction "PD4_6") (pintype "bidirectional"))
    )
    (net (code "14") (name "/MOD_3") (class "Default")
      (node (ref "Q6") (pin "G") (pinfunction "G_G") (pintype "passive"))
      (node (ref "R11") (pin "2") (pinfunction "2_2") (pintype "passive"))
      (node (ref "U1") (pin "11") (pinfunction "PD5_11") (pintype "bidirectional"))
    )
    (net (code "15") (name "/MOD_4") (class "Default")
      (node (ref "Q8") (pin "G") (pinfunction "G_G") (pintype "passive"))
      (node (ref "R14") (pin "2") (pinfunction "2_2") (pintype "passive"))
      (node (ref "U1") (pin "12") (pinfunction "PD6_12") (pintype "bidirectional"))
    )
    (net (code "16") (name "/MOD_5") (class "Default")
      (node (ref "Q10") (pin "G") (pinfunction "G_G") (pintype "passive"))
      (node (ref "R17") (pin "2") (pinfunction "2_2") (pintype "passive"))
      (node (ref "U1") (pin "13") (pinfunction "PD7_13") (pintype "bidirectional"))
    )
    (net (code "17") (name "/MOD_6") (class "Default")
      (node (ref "Q12") (pin "G") (pinfunction "G_G") (pintype "passive"))
      (node (ref "R20") (pin "2") (pinfunction "2_2") (pintype "passive"))
      (node (ref "U1") (pin "14") (pinfunction "PB0_14") (pintype "bidirectional"))
    )
    (net (code "18") (name "/MOD_7") (class "Default")
      (node (ref "Q14") (pin "G") (pinfunction "G_G") (pintype "passive"))
      (node (ref "R25") (pin "2") (pinfunction "2_2") (pintype "passive"))
      (node (ref "U1") (pin "15") (pinfunction "PB1_15") (pintype "bidirectional"))
    )
    (net (code "19") (name "/MOD_8") (class "Default")
      (node (ref "Q16") (pin "G") (pinfunction "G_G") (pintype "passive"))
      (node (ref "R28") (pin "2") (pinfunction "2_2") (pintype "passive"))
      (node (ref "U1") (pin "16") (pinfunction "PB2_16") (pintype "bidirectional"))
    )
    (net (code "20") (name "/MOD_9{slash}MOSI") (class "Default")
      (node (ref "PRG_HEADER") (pin "1") (pinfunction "1_1") (pintype "passive"))
      (node (ref "Q18") (pin "G") (pinfunction "G_G") (pintype "passive"))
      (node (ref "R31") (pin "2") (pinfunction "2_2") (pintype "passive"))
      (node (ref "U1") (pin "17") (pinfunction "PB3_17") (pintype "bidirectional"))
    )
    (net (code "21") (name "/MOD_10{slash}MISO") (class "Default")
      (node (ref "PRG_HEADER") (pin "9") (pinfunction "9_9") (pintype "passive"))
      (node (ref "Q20") (pin "G") (pinfunction "G_G") (pintype "passive"))
      (node (ref "R34") (pin "2") (pinfunction "2_2") (pintype "passive"))
      (node (ref "U1") (pin "18") (pinfunction "PB4_18") (pintype "bidirectional"))
    )
    (net (code "22") (name "/MOD_11") (class "Default")
      (node (ref "Q22") (pin "G") (pinfunction "G_G") (pintype "passive"))
      (node (ref "R37") (pin "2") (pinfunction "2_2") (pintype "passive"))
      (node (ref "U1") (pin "23") (pinfunction "PC0_23") (pintype "bidirectional"))
    )
    (net (code "23") (name "/MOD_12") (class "Default")
      (node (ref "Q24") (pin "G") (pinfunction "G_G") (pintype "passive"))
      (node (ref "R47") (pin "2") (pinfunction "2_2") (pintype "passive"))
      (node (ref "U1") (pin "24") (pinfunction "PC1_24") (pintype "bidirectional"))
    )
    (net (code "24") (name "/MOD_13") (class "Default")
      (node (ref "Q26") (pin "G") (pinfunction "G_G") (pintype "passive"))
      (node (ref "R50") (pin "2") (pinfunction "2_2") (pintype "passive"))
      (node (ref "U1") (pin "25") (pinfunction "PC2_25") (pintype "bidirectional"))
    )
    (net (code "25") (name "/MOD_14") (class "Default")
      (node (ref "Q28") (pin "G") (pinfunction "G_G") (pintype "passive"))
      (node (ref "R53") (pin "2") (pinfunction "2_2") (pintype "passive"))
      (node (ref "U1") (pin "26") (pinfunction "PC3_26") (pintype "bidirectional"))
    )
    (net (code "26") (name "/MOD_15") (class "Default")
      (node (ref "Q30") (pin "G") (pinfunction "G_G") (pintype "passive"))
      (node (ref "R56") (pin "2") (pinfunction "2_2") (pintype "passive"))
      (node (ref "U1") (pin "27") (pinfunction "PC4_27") (pintype "bidirectional"))
    )
    (net (code "27") (name "/MOD_16") (class "Default")
      (node (ref "Q32") (pin "G") (pinfunction "G_G") (pintype "passive"))
      (node (ref "R59") (pin "2") (pinfunction "2_2") (pintype "passive"))
      (node (ref "U1") (pin "28") (pinfunction "PC5_28") (pintype "bidirectional"))
    )
    (net (code "28") (name "/N$37") (class "Default")
      (node (ref "C12") (pin "2") (pinfunction "2_2") (pintype "passive"))
      (node (ref "IC1") (pin "11") (pinfunction "11_11") (pintype "passive"))
      (node (ref "IC1") (pin "14") (pinfunction "14_14") (pintype "passive"))
    )
    (net (code "29") (name "/POWER_IN+") (class "Default")
      (node (ref "D12") (pin "A") (pinfunction "A_A") (pintype "passive"))
      (node (ref "D13") (pin "C") (pinfunction "C_C") (pintype "passive"))
      (node (ref "D16") (pin "A") (pinfunction "A_A") (pintype "passive"))
      (node (ref "D17") (pin "C") (pinfunction "C_C") (pintype "passive"))
      (node (ref "D3") (pin "A") (pinfunction "A_A") (pintype "passive"))
      (node (ref "D4") (pin "C") (pinfunction "C_C") (pintype "passive"))
      (node (ref "D6") (pin "A") (pinfunction "A_A") (pintype "passive"))
      (node (ref "D7") (pin "C") (pinfunction "C_C") (pintype "passive"))
      (node (ref "POWER_IN") (pin "2") (pinfunction "KL_2") (pintype "passive"))
    )
    (net (code "30") (name "/POWER_IN-") (class "Default")
      (node (ref "D1") (pin "A") (pinfunction "A_A") (pintype "passive"))
      (node (ref "D10") (pin "A") (pinfunction "A_A") (pintype "passive"))
      (node (ref "D11") (pin "C") (pinfunction "C_C") (pintype "passive"))
      (node (ref "D14") (pin "A") (pinfunction "A_A") (pintype "passive"))
      (node (ref "D15") (pin "C") (pinfunction "C_C") (pintype "passive"))
      (node (ref "D2") (pin "C") (pinfunction "C_C") (pintype "passive"))
      (node (ref "D8") (pin "A") (pinfunction "A_A") (pintype "passive"))
      (node (ref "D9") (pin "C") (pinfunction "C_C") (pintype "passive"))
      (node (ref "POWER_IN") (pin "1") (pinfunction "KL_1") (pintype "passive"))
    )
    (net (code "31") (name "/RESET") (class "Default")
      (node (ref "C10") (pin "1") (pinfunction "1_1") (pintype "passive"))
      (node (ref "PRG_HEADER") (pin "5") (pinfunction "5_5") (pintype "passive"))
    )
    (net (code "32") (name "/SCK") (class "Default")
      (node (ref "PRG_HEADER") (pin "7") (pinfunction "7_7") (pintype "passive"))
      (node (ref "R41") (pin "2") (pinfunction "2_2") (pintype "passive"))
      (node (ref "U1") (pin "19") (pinfunction "PB5_19") (pintype "bidirectional"))
    )
    (net (code "33") (name "Net-(3,3K-Pad1)") (class "Default")
      (node (ref "3,3K") (pin "1") (pinfunction "1_1") (pintype "passive"))
      (node (ref "Q3") (pin "G") (pinfunction "G_G") (pintype "passive"))
      (node (ref "R44") (pin "2") (pinfunction "2_2") (pintype "passive"))
    )
    (net (code "34") (name "Net-(3,3K-Pad2)") (class "Default")
      (node (ref "3,3K") (pin "2") (pinfunction "2_2") (pintype "passive"))
      (node (ref "JP4") (pin "2") (pinfunction "2_2") (pintype "passive"))
      (node (ref "Q3") (pin "S") (pinfunction "S_S") (pintype "passive"))
    )
    (net (code "35") (name "Net-(3,3K1-Pad1)") (class "Default")
      (node (ref "3,3K1") (pin "1") (pinfunction "1_1") (pintype "passive"))
      (node (ref "Q5") (pin "G") (pinfunction "G_G") (pintype "passive"))
      (node (ref "R7") (pin "2") (pinfunction "2_2") (pintype "passive"))
    )
    (net (code "36") (name "Net-(3,3K1-Pad2)") (class "Default")
      (node (ref "3,3K1") (pin "2") (pinfunction "2_2") (pintype "passive"))
      (node (ref "JP2") (pin "2") (pinfunction "2_2") (pintype "passive"))
      (node (ref "Q5") (pin "S") (pinfunction "S_S") (pintype "passive"))
    )
    (net (code "37") (name "Net-(3,3K2-Pad1)") (class "Default")
      (node (ref "3,3K2") (pin "1") (pinfunction "1_1") (pintype "passive"))
      (node (ref "Q7") (pin "G") (pinfunction "G_G") (pintype "passive"))
      (node (ref "R10") (pin "2") (pinfunction "2_2") (pintype "passive"))
    )
    (net (code "38") (name "Net-(3,3K2-Pad2)") (class "Default")
      (node (ref "3,3K2") (pin "2") (pinfunction "2_2") (pintype "passive"))
      (node (ref "JP6") (pin "2") (pinfunction "2_2") (pintype "passive"))
      (node (ref "Q7") (pin "S") (pinfunction "S_S") (pintype "passive"))
    )
    (net (code "39") (name "Net-(3,3K3-Pad1)") (class "Default")
      (node (ref "3,3K3") (pin "1") (pinfunction "1_1") (pintype "passive"))
      (node (ref "Q9") (pin "G") (pinfunction "G_G") (pintype "passive"))
      (node (ref "R13") (pin "2") (pinfunction "2_2") (pintype "passive"))
    )
    (net (code "40") (name "Net-(3,3K3-Pad2)") (class "Default")
      (node (ref "3,3K3") (pin "2") (pinfunction "2_2") (pintype "passive"))
      (node (ref "JP8") (pin "2") (pinfunction "2_2") (pintype "passive"))
      (node (ref "Q9") (pin "S") (pinfunction "S_S") (pintype "passive"))
    )
    (net (code "41") (name "Net-(3,3K4-Pad1)") (class "Default")
      (node (ref "3,3K4") (pin "1") (pinfunction "1_1") (pintype "passive"))
      (node (ref "Q11") (pin "G") (pinfunction "G_G") (pintype "passive"))
      (node (ref "R16") (pin "2") (pinfunction "2_2") (pintype "passive"))
    )
    (net (code "42") (name "Net-(3,3K4-Pad2)") (class "Default")
      (node (ref "3,3K4") (pin "2") (pinfunction "2_2") (pintype "passive"))
      (node (ref "JP10") (pin "2") (pinfunction "2_2") (pintype "passive"))
      (node (ref "Q11") (pin "S") (pinfunction "S_S") (pintype "passive"))
    )
    (net (code "43") (name "Net-(3,3K5-Pad1)") (class "Default")
      (node (ref "3,3K5") (pin "1") (pinfunction "1_1") (pintype "passive"))
      (node (ref "Q13") (pin "G") (pinfunction "G_G") (pintype "passive"))
      (node (ref "R19") (pin "2") (pinfunction "2_2") (pintype "passive"))
    )
    (net (code "44") (name "Net-(3,3K5-Pad2)") (class "Default")
      (node (ref "3,3K5") (pin "2") (pinfunction "2_2") (pintype "passive"))
      (node (ref "JP12") (pin "2") (pinfunction "2_2") (pintype "passive"))
      (node (ref "Q13") (pin "S") (pinfunction "S_S") (pintype "passive"))
    )
    (net (code "45") (name "Net-(3,3K6-Pad1)") (class "Default")
      (node (ref "3,3K6") (pin "1") (pinfunction "1_1") (pintype "passive"))
      (node (ref "Q15") (pin "G") (pinfunction "G_G") (pintype "passive"))
      (node (ref "R24") (pin "2") (pinfunction "2_2") (pintype "passive"))
    )
    (net (code "46") (name "Net-(3,3K6-Pad2)") (class "Default")
      (node (ref "3,3K6") (pin "2") (pinfunction "2_2") (pintype "passive"))
      (node (ref "JP14") (pin "2") (pinfunction "2_2") (pintype "passive"))
      (node (ref "Q15") (pin "S") (pinfunction "S_S") (pintype "passive"))
    )
    (net (code "47") (name "Net-(3,3K7-Pad1)") (class "Default")
      (node (ref "3,3K7") (pin "1") (pinfunction "1_1") (pintype "passive"))
      (node (ref "Q17") (pin "G") (pinfunction "G_G") (pintype "passive"))
      (node (ref "R27") (pin "2") (pinfunction "2_2") (pintype "passive"))
    )
    (net (code "48") (name "Net-(3,3K7-Pad2)") (class "Default")
      (node (ref "3,3K7") (pin "2") (pinfunction "2_2") (pintype "passive"))
      (node (ref "JP16") (pin "2") (pinfunction "2_2") (pintype "passive"))
      (node (ref "Q17") (pin "S") (pinfunction "S_S") (pintype "passive"))
    )
    (net (code "49") (name "Net-(3,3K8-Pad1)") (class "Default")
      (node (ref "3,3K8") (pin "1") (pinfunction "1_1") (pintype "passive"))
      (node (ref "Q19") (pin "G") (pinfunction "G_G") (pintype "passive"))
      (node (ref "R30") (pin "2") (pinfunction "2_2") (pintype "passive"))
    )
    (net (code "50") (name "Net-(3,3K8-Pad2)") (class "Default")
      (node (ref "3,3K8") (pin "2") (pinfunction "2_2") (pintype "passive"))
      (node (ref "JP18") (pin "2") (pinfunction "2_2") (pintype "passive"))
      (node (ref "Q19") (pin "S") (pinfunction "S_S") (pintype "passive"))
    )
    (net (code "51") (name "Net-(3,3K9-Pad1)") (class "Default")
      (node (ref "3,3K9") (pin "1") (pinfunction "1_1") (pintype "passive"))
      (node (ref "Q21") (pin "G") (pinfunction "G_G") (pintype "passive"))
      (node (ref "R33") (pin "2") (pinfunction "2_2") (pintype "passive"))
    )
    (net (code "52") (name "Net-(3,3K9-Pad2)") (class "Default")
      (node (ref "3,3K9") (pin "2") (pinfunction "2_2") (pintype "passive"))
      (node (ref "JP20") (pin "2") (pinfunction "2_2") (pintype "passive"))
      (node (ref "Q21") (pin "S") (pinfunction "S_S") (pintype "passive"))
    )
    (net (code "53") (name "Net-(3,3K10-Pad1)") (class "Default")
      (node (ref "3,3K10") (pin "1") (pinfunction "1_1") (pintype "passive"))
      (node (ref "Q23") (pin "G") (pinfunction "G_G") (pintype "passive"))
      (node (ref "R36") (pin "2") (pinfunction "2_2") (pintype "passive"))
    )
    (net (code "54") (name "Net-(3,3K10-Pad2)") (class "Default")
      (node (ref "3,3K10") (pin "2") (pinfunction "2_2") (pintype "passive"))
      (node (ref "JP22") (pin "2") (pinfunction "2_2") (pintype "passive"))
      (node (ref "Q23") (pin "S") (pinfunction "S_S") (pintype "passive"))
    )
    (net (code "55") (name "Net-(3,3K11-Pad1)") (class "Default")
      (node (ref "3,3K11") (pin "1") (pinfunction "1_1") (pintype "passive"))
      (node (ref "Q25") (pin "G") (pinfunction "G_G") (pintype "passive"))
      (node (ref "R45") (pin "2") (pinfunction "2_2") (pintype "passive"))
    )
    (net (code "56") (name "Net-(3,3K11-Pad2)") (class "Default")
      (node (ref "3,3K11") (pin "2") (pinfunction "2_2") (pintype "passive"))
      (node (ref "JP24") (pin "2") (pinfunction "2_2") (pintype "passive"))
      (node (ref "Q25") (pin "S") (pinfunction "S_S") (pintype "passive"))
    )
    (net (code "57") (name "Net-(3,3K12-Pad1)") (class "Default")
      (node (ref "3,3K12") (pin "1") (pinfunction "1_1") (pintype "passive"))
      (node (ref "Q27") (pin "G") (pinfunction "G_G") (pintype "passive"))
      (node (ref "R49") (pin "2") (pinfunction "2_2") (pintype "passive"))
    )
    (net (code "58") (name "Net-(3,3K12-Pad2)") (class "Default")
      (node (ref "3,3K12") (pin "2") (pinfunction "2_2") (pintype "passive"))
      (node (ref "JP26") (pin "2") (pinfunction "2_2") (pintype "passive"))
      (node (ref "Q27") (pin "S") (pinfunction "S_S") (pintype "passive"))
    )
    (net (code "59") (name "Net-(3,3K13-Pad1)") (class "Default")
      (node (ref "3,3K13") (pin "1") (pinfunction "1_1") (pintype "passive"))
      (node (ref "Q29") (pin "G") (pinfunction "G_G") (pintype "passive"))
      (node (ref "R52") (pin "2") (pinfunction "2_2") (pintype "passive"))
    )
    (net (code "60") (name "Net-(3,3K13-Pad2)") (class "Default")
      (node (ref "3,3K13") (pin "2") (pinfunction "2_2") (pintype "passive"))
      (node (ref "JP28") (pin "2") (pinfunction "2_2") (pintype "passive"))
      (node (ref "Q29") (pin "S") (pinfunction "S_S") (pintype "passive"))
    )
    (net (code "61") (name "Net-(3,3K14-Pad1)") (class "Default")
      (node (ref "3,3K14") (pin "1") (pinfunction "1_1") (pintype "passive"))
      (node (ref "Q31") (pin "G") (pinfunction "G_G") (pintype "passive"))
      (node (ref "R55") (pin "2") (pinfunction "2_2") (pintype "passive"))
    )
    (net (code "62") (name "Net-(3,3K14-Pad2)") (class "Default")
      (node (ref "3,3K14") (pin "2") (pinfunction "2_2") (pintype "passive"))
      (node (ref "JP30") (pin "2") (pinfunction "2_2") (pintype "passive"))
      (node (ref "Q31") (pin "S") (pinfunction "S_S") (pintype "passive"))
    )
    (net (code "63") (name "Net-(3,3K15-Pad1)") (class "Default")
      (node (ref "3,3K15") (pin "1") (pinfunction "1_1") (pintype "passive"))
      (node (ref "Q33") (pin "G") (pinfunction "G_G") (pintype "passive"))
      (node (ref "R58") (pin "2") (pinfunction "2_2") (pintype "passive"))
    )
    (net (code "64") (name "Net-(3,3K15-Pad2)") (class "Default")
      (node (ref "3,3K15") (pin "2") (pinfunction "2_2") (pintype "passive"))
      (node (ref "JP32") (pin "2") (pinfunction "2_2") (pintype "passive"))
      (node (ref "Q33") (pin "S") (pinfunction "S_S") (pintype "passive"))
    )
    (net (code "65") (name "Net-(D19-PadA)") (class "Default")
      (node (ref "D19") (pin "A") (pinfunction "A_A") (pintype "passive"))
      (node (ref "PRG_HEADER") (pin "2") (pinfunction "2_2") (pintype "passive"))
    )
    (net (code "66") (name "Net-(DCC_INA-KL)") (class "Default")
      (node (ref "DCC_IN") (pin "1") (pinfunction "KL_1") (pintype "passive"))
      (node (ref "R3") (pin "1") (pinfunction "1_1") (pintype "passive"))
    )
    (net (code "67") (name "Net-(DCC_INB-KL)") (class "Default")
      (node (ref "D5") (pin "A") (pinfunction "A_A") (pintype "passive"))
      (node (ref "DCC_IN") (pin "2") (pinfunction "KL_2") (pintype "passive"))
      (node (ref "OK1") (pin "3") (pinfunction "C_3") (pintype "passive"))
    )
    (net (code "68") (name "Net-(IC1-Pad4)") (class "Default")
      (node (ref "IC1") (pin "4") (pinfunction "4_4") (pintype "passive"))
      (node (ref "R43") (pin "1") (pinfunction "1_1") (pintype "passive"))
    )
    (net (code "69") (name "Net-(LED1-PadA)") (class "Default")
      (node (ref "LED1") (pin "A") (pinfunction "A_A") (pintype "passive"))
      (node (ref "R4") (pin "1") (pinfunction "1_1") (pintype "passive"))
    )
    (net (code "70") (name "Net-(LED2-PadA)") (class "Default")
      (node (ref "LED2") (pin "A") (pinfunction "A_A") (pintype "passive"))
      (node (ref "R5") (pin "1") (pinfunction "1_1") (pintype "passive"))
    )
    (net (code "71") (name "Net-(LED3-PadA)") (class "Default")
      (node (ref "LED3") (pin "A") (pinfunction "A_A") (pintype "passive"))
      (node (ref "R6") (pin "1") (pinfunction "1_1") (pintype "passive"))
    )
    (net (code "72") (name "Net-(LED4-PadA)") (class "Default")
      (node (ref "LED4") (pin "A") (pinfunction "A_A") (pintype "passive"))
      (node (ref "R9") (pin "1") (pinfunction "1_1") (pintype "passive"))
    )
    (net (code "73") (name "Net-(LED5-PadA)") (class "Default")
      (node (ref "LED5") (pin "A") (pinfunction "A_A") (pintype "passive"))
      (node (ref "R12") (pin "1") (pinfunction "1_1") (pintype "passive"))
    )
    (net (code "74") (name "Net-(LED6-PadA)") (class "Default")
      (node (ref "LED6") (pin "A") (pinfunction "A_A") (pintype "passive"))
      (node (ref "R15") (pin "1") (pinfunction "1_1") (pintype "passive"))
    )
    (net (code "75") (name "Net-(LED7-PadA)") (class "Default")
      (node (ref "LED7") (pin "A") (pinfunction "A_A") (pintype "passive"))
      (node (ref "R18") (pin "1") (pinfunction "1_1") (pintype "passive"))
    )
    (net (code "76") (name "Net-(LED8-PadA)") (class "Default")
      (node (ref "LED8") (pin "A") (pinfunction "A_A") (pintype "passive"))
      (node (ref "R23") (pin "1") (pinfunction "1_1") (pintype "passive"))
    )
    (net (code "77") (name "Net-(LED9-PadA)") (class "Default")
      (node (ref "LED9") (pin "A") (pinfunction "A_A") (pintype "passive"))
      (node (ref "R26") (pin "1") (pinfunction "1_1") (pintype "passive"))
    )
    (net (code "78") (name "Net-(LED10-PadA)") (class "Default")
      (node (ref "LED10") (pin "A") (pinfunction "A_A") (pintype "passive"))
      (node (ref "R29") (pin "1") (pinfunction "1_1") (pintype "passive"))
    )
    (net (code "79") (name "Net-(LED11-PadA)") (class "Default")
      (node (ref "LED11") (pin "A") (pinfunction "A_A") (pintype "passive"))
      (node (ref "R32") (pin "1") (pinfunction "1_1") (pintype "passive"))
    )
    (net (code "80") (name "Net-(LED12-PadA)") (class "Default")
      (node (ref "LED12") (pin "A") (pinfunction "A_A") (pintype "passive"))
      (node (ref "R35") (pin "1") (pinfunction "1_1") (pintype "passive"))
    )
    (net (code "81") (name "Net-(LED13-PadA)") (class "Default")
      (node (ref "LED13") (pin "A") (pinfunction "A_A") (pintype "passive"))
      (node (ref "R38") (pin "1") (pinfunction "1_1") (pintype "passive"))
    )
    (net (code "82") (name "Net-(LED14-PadA)") (class "Default")
      (node (ref "LED14") (pin "A") (pinfunction "A_A") (pintype "passive"))
      (node (ref "R48") (pin "1") (pinfunction "1_1") (pintype "passive"))
    )
    (net (code "83") (name "Net-(LED15-PadA)") (class "Default")
      (node (ref "LED15") (pin "A") (pinfunction "A_A") (pintype "passive"))
      (node (ref "R51") (pin "1") (pinfunction "1_1") (pintype "passive"))
    )
    (net (code "84") (name "Net-(LED16-PadA)") (class "Default")
      (node (ref "LED16") (pin "A") (pinfunction "A_A") (pintype "passive"))
      (node (ref "R54") (pin "1") (pinfunction "1_1") (pintype "passive"))
    )
    (net (code "85") (name "Net-(LED17-PadA)") (class "Default")
      (node (ref "LED17") (pin "A") (pinfunction "A_A") (pintype "passive"))
      (node (ref "R57") (pin "1") (pinfunction "1_1") (pintype "passive"))
    )
    (net (code "86") (name "Net-(LED18-PadA)") (class "Default")
      (node (ref "LED18") (pin "A") (pinfunction "A_A") (pintype "passive"))
      (node (ref "R21") (pin "1") (pinfunction "1_1") (pintype "passive"))
    )
    (net (code "87") (name "Net-(LED19-PadA)") (class "Default")
      (node (ref "LED19") (pin "A") (pinfunction "A_A") (pintype "passive"))
      (node (ref "R22") (pin "1") (pinfunction "1_1") (pintype "passive"))
    )
    (net (code "88") (name "Net-(LED20-PadA)") (class "Default")
      (node (ref "LED20") (pin "A") (pinfunction "A_A") (pintype "passive"))
      (node (ref "R40") (pin "1") (pinfunction "1_1") (pintype "passive"))
    )
    (net (code "89") (name "Net-(LED21-PadA)") (class "Default")
      (node (ref "LED21") (pin "A") (pinfunction "A_A") (pintype "passive"))
      (node (ref "R41") (pin "1") (pinfunction "1_1") (pintype "passive"))
    )
    (net (code "90") (name "Net-(LED22-PadA)") (class "Default")
      (node (ref "LED22") (pin "A") (pinfunction "A_A") (pintype "passive"))
      (node (ref "R42") (pin "1") (pinfunction "1_1") (pintype "passive"))
    )
    (net (code "91") (name "Net-(OK1-A)") (class "Default")
      (node (ref "D5") (pin "C") (pinfunction "C_C") (pintype "passive"))
      (node (ref "OK1") (pin "2") (pinfunction "A_2") (pintype "passive"))
      (node (ref "R3") (pin "2") (pinfunction "2_2") (pintype "passive"))
    )
    (net (code "92") (name "Net-(OK1-VE)") (class "Default")
      (node (ref "OK1") (pin "7") (pinfunction "VE_7") (pintype "passive"))
      (node (ref "R1") (pin "1") (pinfunction "1_1") (pintype "passive"))
    )
    (net (code "93") (name "Net-(Q2-PadD)") (class "Default")
      (node (ref "Q2") (pin "D") (pinfunction "D_D") (pintype "passive"))
      (node (ref "R44") (pin "1") (pinfunction "1_1") (pintype "passive"))
    )
    (net (code "94") (name "Net-(Q4-PadD)") (class "Default")
      (node (ref "Q4") (pin "D") (pinfunction "D_D") (pintype "passive"))
      (node (ref "R7") (pin "1") (pinfunction "1_1") (pintype "passive"))
    )
    (net (code "95") (name "Net-(Q6-PadD)") (class "Default")
      (node (ref "Q6") (pin "D") (pinfunction "D_D") (pintype "passive"))
      (node (ref "R10") (pin "1") (pinfunction "1_1") (pintype "passive"))
    )
    (net (code "96") (name "Net-(Q8-PadD)") (class "Default")
      (node (ref "Q8") (pin "D") (pinfunction "D_D") (pintype "passive"))
      (node (ref "R13") (pin "1") (pinfunction "1_1") (pintype "passive"))
    )
    (net (code "97") (name "Net-(Q10-PadD)") (class "Default")
      (node (ref "Q10") (pin "D") (pinfunction "D_D") (pintype "passive"))
      (node (ref "R16") (pin "1") (pinfunction "1_1") (pintype "passive"))
    )
    (net (code "98") (name "Net-(Q12-PadD)") (class "Default")
      (node (ref "Q12") (pin "D") (pinfunction "D_D") (pintype "passive"))
      (node (ref "R19") (pin "1") (pinfunction "1_1") (pintype "passive"))
    )
    (net (code "99") (name "Net-(Q14-PadD)") (class "Default")
      (node (ref "Q14") (pin "D") (pinfunction "D_D") (pintype "passive"))
      (node (ref "R24") (pin "1") (pinfunction "1_1") (pintype "passive"))
    )
    (net (code "100") (name "Net-(Q16-PadD)") (class "Default")
      (node (ref "Q16") (pin "D") (pinfunction "D_D") (pintype "passive"))
      (node (ref "R27") (pin "1") (pinfunction "1_1") (pintype "passive"))
    )
    (net (code "101") (name "Net-(Q18-PadD)") (class "Default")
      (node (ref "Q18") (pin "D") (pinfunction "D_D") (pintype "passive"))
      (node (ref "R30") (pin "1") (pinfunction "1_1") (pintype "passive"))
    )
    (net (code "102") (name "Net-(Q20-PadD)") (class "Default")
      (node (ref "Q20") (pin "D") (pinfunction "D_D") (pintype "passive"))
      (node (ref "R33") (pin "1") (pinfunction "1_1") (pintype "passive"))
    )
    (net (code "103") (name "Net-(Q22-PadD)") (class "Default")
      (node (ref "Q22") (pin "D") (pinfunction "D_D") (pintype "passive"))
      (node (ref "R36") (pin "1") (pinfunction "1_1") (pintype "passive"))
    )
    (net (code "104") (name "Net-(Q24-PadD)") (class "Default")
      (node (ref "Q24") (pin "D") (pinfunction "D_D") (pintype "passive"))
      (node (ref "R45") (pin "1") (pinfunction "1_1") (pintype "passive"))
    )
    (net (code "105") (name "Net-(Q26-PadD)") (class "Default")
      (node (ref "Q26") (pin "D") (pinfunction "D_D") (pintype "passive"))
      (node (ref "R49") (pin "1") (pinfunction "1_1") (pintype "passive"))
    )
    (net (code "106") (name "Net-(Q28-PadD)") (class "Default")
      (node (ref "Q28") (pin "D") (pinfunction "D_D") (pintype "passive"))
      (node (ref "R52") (pin "1") (pinfunction "1_1") (pintype "passive"))
    )
    (net (code "107") (name "Net-(Q30-PadD)") (class "Default")
      (node (ref "Q30") (pin "D") (pinfunction "D_D") (pintype "passive"))
      (node (ref "R55") (pin "1") (pinfunction "1_1") (pintype "passive"))
    )
    (net (code "108") (name "Net-(Q32-PadD)") (class "Default")
      (node (ref "Q32") (pin "D") (pinfunction "D_D") (pintype "passive"))
      (node (ref "R58") (pin "1") (pinfunction "1_1") (pintype "passive"))
    )
    (net (code "109") (name "Net-(S1-S)") (class "Default")
      (node (ref "C10") (pin "2") (pinfunction "2_2") (pintype "passive"))
      (node (ref "R39") (pin "2") (pinfunction "2_2") (pintype "passive"))
      (node (ref "S1") (pin "1") (pinfunction "S_1") (pintype "passive"))
      (node (ref "U1") (pin "1") (pinfunction "PC6/~{RESET}_1") (pintype "bidirectional"))
    )
    (net (code "110") (name "Net-(U$1-D+)") (class "Default")
      (node (ref "IC1") (pin "13") (pinfunction "13_13") (pintype "passive"))
      (node (ref "U$1") (pin "3") (pinfunction "D+_3") (pintype "bidirectional"))
    )
    (net (code "111") (name "Net-(U$1-D-)") (class "Default")
      (node (ref "IC1") (pin "12") (pinfunction "12_12") (pintype "passive"))
      (node (ref "U$1") (pin "2") (pinfunction "D-_2") (pintype "bidirectional"))
    )
    (net (code "112") (name "Net-(U1-AREF)") (class "Default")
      (node (ref "C11") (pin "2") (pinfunction "2_2") (pintype "passive"))
      (node (ref "U1") (pin "21") (pinfunction "AREF_21") (pintype "input"))
    )
    (net (code "113") (name "Net-(U1-PB6)") (class "Default")
      (node (ref "C15") (pin "2") (pinfunction "2_2") (pintype "passive"))
      (node (ref "Q1") (pin "2") (pinfunction "2_2") (pintype "passive"))
      (node (ref "U1") (pin "9") (pinfunction "PB6_9") (pintype "bidirectional"))
    )
    (net (code "114") (name "Net-(U1-PB7)") (class "Default")
      (node (ref "C14") (pin "2") (pinfunction "2_2") (pintype "passive"))
      (node (ref "Q1") (pin "1") (pinfunction "1_1") (pintype "passive"))
      (node (ref "U1") (pin "10") (pinfunction "PB7_10") (pintype "bidirectional"))
    )
    (net (code "115") (name "Net-(U1-PD0)") (class "Default")
      (node (ref "IC1") (pin "6") (pinfunction "6_6") (pintype "passive"))
      (node (ref "U1") (pin "2") (pinfunction "PD0_2") (pintype "bidirectional"))
    )
    (net (code "116") (name "Net-(U1-PD1)") (class "Default")
      (node (ref "IC1") (pin "5") (pinfunction "5_5") (pintype "passive"))
      (node (ref "U1") (pin "3") (pinfunction "PD1_3") (pintype "bidirectional"))
    )
    (net (code "117") (name "Net-(X1C-KL)") (class "Default")
      (node (ref "JP1") (pin "3") (pinfunction "3_3") (pintype "passive"))
      (node (ref "Q5") (pin "D") (pinfunction "D_D") (pintype "passive"))
      (node (ref "R6") (pin "2") (pinfunction "2_2") (pintype "passive"))
      (node (ref "X1") (pin "3") (pinfunction "KL_3") (pintype "passive"))
    )
    (net (code "118") (name "Net-(X2C-KL)") (class "Default")
      (node (ref "JP3") (pin "3") (pinfunction "3_3") (pintype "passive"))
      (node (ref "Q3") (pin "D") (pinfunction "D_D") (pintype "passive"))
      (node (ref "R5") (pin "2") (pinfunction "2_2") (pintype "passive"))
      (node (ref "X2") (pin "3") (pinfunction "KL_3") (pintype "passive"))
    )
    (net (code "119") (name "Net-(X3C-KL)") (class "Default")
      (node (ref "JP5") (pin "3") (pinfunction "3_3") (pintype "passive"))
      (node (ref "Q7") (pin "D") (pinfunction "D_D") (pintype "passive"))
      (node (ref "R9") (pin "2") (pinfunction "2_2") (pintype "passive"))
      (node (ref "X3") (pin "3") (pinfunction "KL_3") (pintype "passive"))
    )
    (net (code "120") (name "Net-(X4C-KL)") (class "Default")
      (node (ref "JP7") (pin "3") (pinfunction "3_3") (pintype "passive"))
      (node (ref "Q9") (pin "D") (pinfunction "D_D") (pintype "passive"))
      (node (ref "R12") (pin "2") (pinfunction "2_2") (pintype "passive"))
      (node (ref "X4") (pin "3") (pinfunction "KL_3") (pintype "passive"))
    )
    (net (code "121") (name "Net-(X5C-KL)") (class "Default")
      (node (ref "JP9") (pin "3") (pinfunction "3_3") (pintype "passive"))
      (node (ref "Q11") (pin "D") (pinfunction "D_D") (pintype "passive"))
      (node (ref "R15") (pin "2") (pinfunction "2_2") (pintype "passive"))
      (node (ref "X5") (pin "3") (pinfunction "KL_3") (pintype "passive"))
    )
    (net (code "122") (name "Net-(X6C-KL)") (class "Default")
      (node (ref "JP11") (pin "3") (pinfunction "3_3") (pintype "passive"))
      (node (ref "Q13") (pin "D") (pinfunction "D_D") (pintype "passive"))
      (node (ref "R18") (pin "2") (pinfunction "2_2") (pintype "passive"))
      (node (ref "X6") (pin "3") (pinfunction "KL_3") (pintype "passive"))
    )
    (net (code "123") (name "Net-(X7C-KL)") (class "Default")
      (node (ref "JP13") (pin "3") (pinfunction "3_3") (pintype "passive"))
      (node (ref "Q15") (pin "D") (pinfunction "D_D") (pintype "passive"))
      (node (ref "R23") (pin "2") (pinfunction "2_2") (pintype "passive"))
      (node (ref "X7") (pin "3") (pinfunction "KL_3") (pintype "passive"))
    )
    (net (code "124") (name "Net-(X8C-KL)") (class "Default")
      (node (ref "JP15") (pin "3") (pinfunction "3_3") (pintype "passive"))
      (node (ref "Q17") (pin "D") (pinfunction "D_D") (pintype "passive"))
      (node (ref "R26") (pin "2") (pinfunction "2_2") (pintype "passive"))
      (node (ref "X8") (pin "3") (pinfunction "KL_3") (pintype "passive"))
    )
    (net (code "125") (name "Net-(X9C-KL)") (class "Default")
      (node (ref "JP17") (pin "3") (pinfunction "3_3") (pintype "passive"))
      (node (ref "Q19") (pin "D") (pinfunction "D_D") (pintype "passive"))
      (node (ref "R29") (pin "2") (pinfunction "2_2") (pintype "passive"))
      (node (ref "X9") (pin "3") (pinfunction "KL_3") (pintype "passive"))
    )
    (net (code "126") (name "Net-(X10C-KL)") (class "Default")
      (node (ref "JP19") (pin "3") (pinfunction "3_3") (pintype "passive"))
      (node (ref "Q21") (pin "D") (pinfunction "D_D") (pintype "passive"))
      (node (ref "R32") (pin "2") (pinfunction "2_2") (pintype "passive"))
      (node (ref "X10") (pin "3") (pinfunction "KL_3") (pintype "passive"))
    )
    (net (code "127") (name "Net-(X11C-KL)") (class "Default")
      (node (ref "JP21") (pin "3") (pinfunction "3_3") (pintype "passive"))
      (node (ref "Q23") (pin "D") (pinfunction "D_D") (pintype "passive"))
      (node (ref "R35") (pin "2") (pinfunction "2_2") (pintype "passive"))
      (node (ref "X11") (pin "3") (pinfunction "KL_3") (pintype "passive"))
    )
    (net (code "128") (name "Net-(X12C-KL)") (class "Default")
      (node (ref "JP23") (pin "3") (pinfunction "3_3") (pintype "passive"))
      (node (ref "Q25") (pin "D") (pinfunction "D_D") (pintype "passive"))
      (node (ref "R38") (pin "2") (pinfunction "2_2") (pintype "passive"))
      (node (ref "X12") (pin "3") (pinfunction "KL_3") (pintype "passive"))
    )
    (net (code "129") (name "Net-(X13C-KL)") (class "Default")
      (node (ref "JP25") (pin "3") (pinfunction "3_3") (pintype "passive"))
      (node (ref "Q27") (pin "D") (pinfunction "D_D") (pintype "passive"))
      (node (ref "R48") (pin "2") (pinfunction "2_2") (pintype "passive"))
      (node (ref "X13") (pin "3") (pinfunction "KL_3") (pintype "passive"))
    )
    (net (code "130") (name "Net-(X14C-KL)") (class "Default")
      (node (ref "JP27") (pin "3") (pinfunction "3_3") (pintype "passive"))
      (node (ref "Q29") (pin "D") (pinfunction "D_D") (pintype "passive"))
      (node (ref "R51") (pin "2") (pinfunction "2_2") (pintype "passive"))
      (node (ref "X14") (pin "3") (pinfunction "KL_3") (pintype "passive"))
    )
    (net (code "131") (name "Net-(X15C-KL)") (class "Default")
      (node (ref "JP29") (pin "3") (pinfunction "3_3") (pintype "passive"))
      (node (ref "Q31") (pin "D") (pinfunction "D_D") (pintype "passive"))
      (node (ref "R54") (pin "2") (pinfunction "2_2") (pintype "passive"))
      (node (ref "X15") (pin "3") (pinfunction "KL_3") (pintype "passive"))
    )
    (net (code "132") (name "Net-(X16C-KL)") (class "Default")
      (node (ref "JP31") (pin "3") (pinfunction "3_3") (pintype "passive"))
      (node (ref "Q33") (pin "D") (pinfunction "D_D") (pintype "passive"))
      (node (ref "R57") (pin "2") (pinfunction "2_2") (pintype "passive"))
      (node (ref "X16") (pin "3") (pinfunction "KL_3") (pintype "passive"))
    )
    (net (code "133") (name "unconnected-(IC1-Pad2)") (class "Default")
      (node (ref "IC1") (pin "2") (pinfunction "2_2") (pintype "passive"))
    )
    (net (code "134") (name "unconnected-(IC1-Pad3)") (class "Default")
      (node (ref "IC1") (pin "3") (pinfunction "3_3") (pintype "passive"))
    )
    (net (code "135") (name "unconnected-(IC1-Pad7)") (class "Default")
      (node (ref "IC1") (pin "7") (pinfunction "7_7") (pintype "passive"))
    )
    (net (code "136") (name "unconnected-(IC1-Pad8)") (class "Default")
      (node (ref "IC1") (pin "8") (pinfunction "8_8") (pintype "passive"))
    )
    (net (code "137") (name "unconnected-(IC1-Pad9)") (class "Default")
      (node (ref "IC1") (pin "9") (pinfunction "9_9") (pintype "passive"))
    )
    (net (code "138") (name "unconnected-(IC1-Pad10)") (class "Default")
      (node (ref "IC1") (pin "10") (pinfunction "10_10") (pintype "passive"))
    )
    (net (code "139") (name "unconnected-(PRG_HEADER-Pad3)") (class "Default")
      (node (ref "PRG_HEADER") (pin "3") (pinfunction "3_3") (pintype "passive"))
    )
    (net (code "140") (name "unconnected-(S1-P1-Pad4)") (class "Default")
      (node (ref "S1") (pin "4") (pinfunction "P1_4") (pintype "passive"))
    )
    (net (code "141") (name "unconnected-(S1-S1-Pad2)") (class "Default")
      (node (ref "S1") (pin "2") (pinfunction "S1_2") (pintype "passive"))
    )
    (net (code "142") (name "unconnected-(U$1-ID-Pad4)") (class "Default")
      (node (ref "U$1") (pin "4") (pinfunction "ID_4") (pintype "bidirectional"))
    )
  )
)
